# ProPrj_chesslink-v1-pcb_2025-04-17.net
KiCad netlist of a schematic drawn in EasyEDA Pro
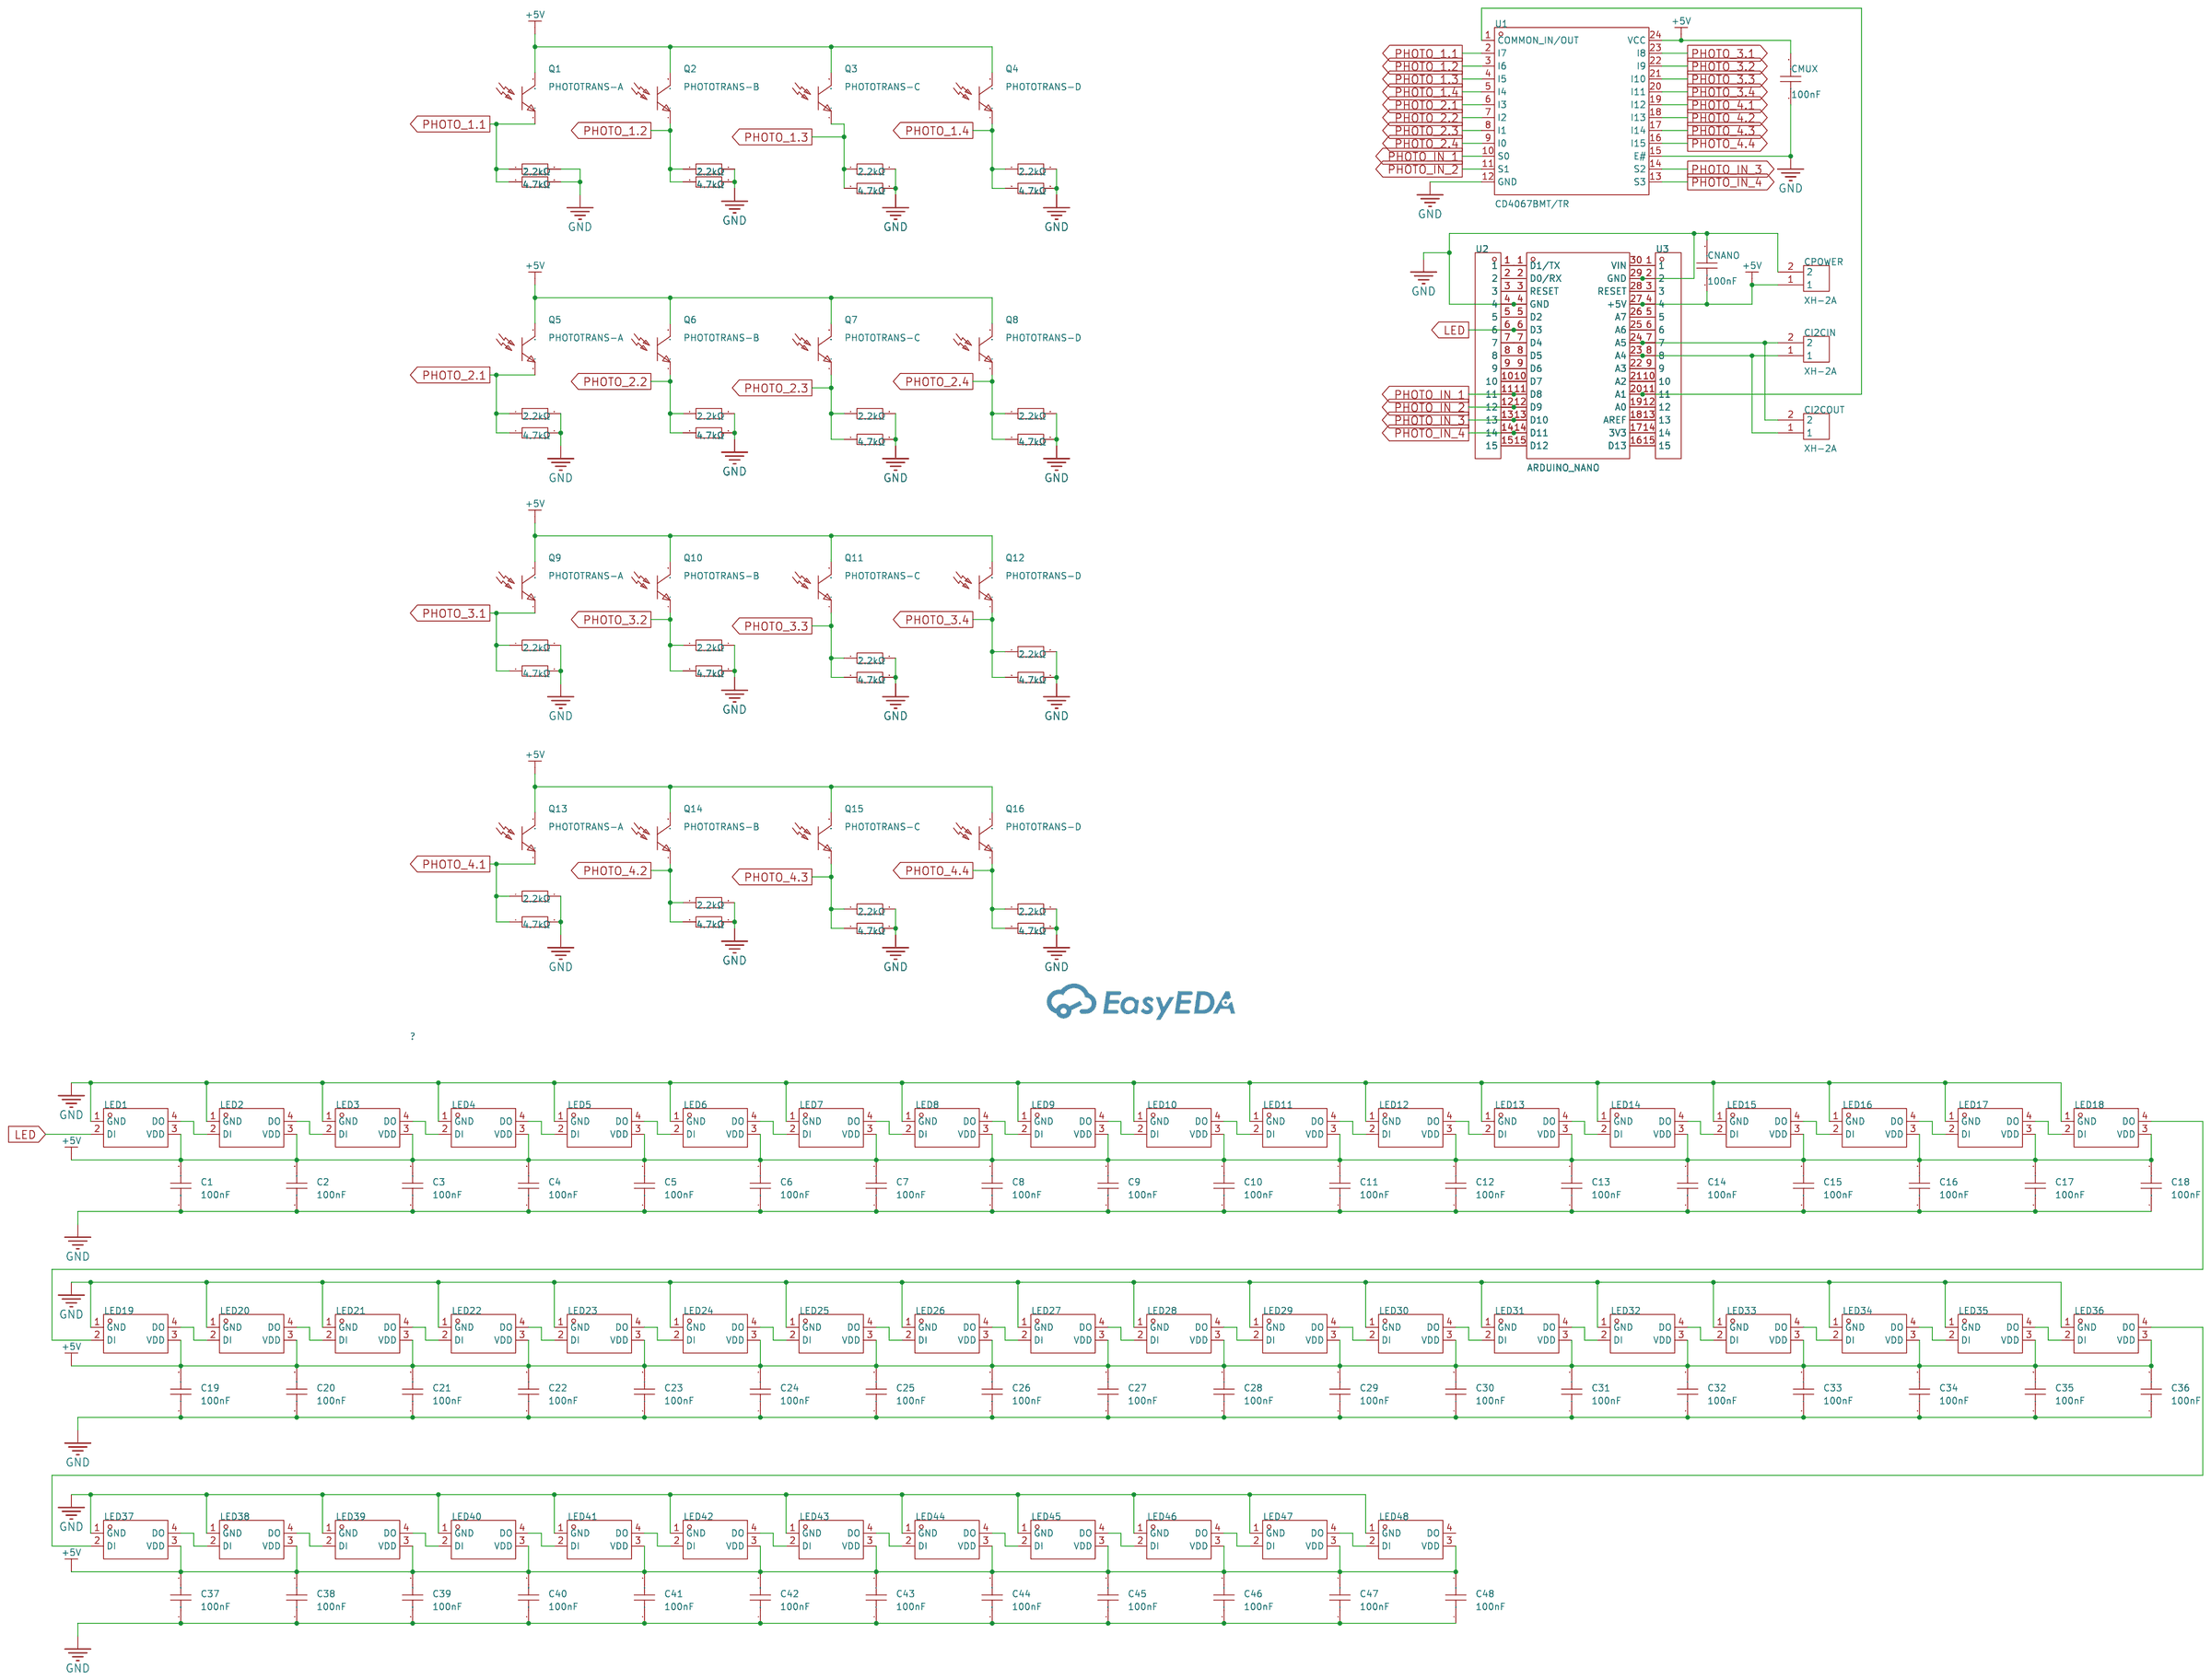
[diagram p0: schematic sheet]

(export (version "E")
  (design (tool "Eeschema 10.0.6"))
  (components
    (comp (ref "ArduinoNano")
      (value "ARDUINO_NANO")
      (footprint "easyedapro:COMM-TH_ARDUINO_NANO")
      (libsource (lib "easyedapro") (part "ARDUINO_NANO"))
    )
    (comp (ref "C1")
      (value "100nF")
      (footprint "easyedapro:C0402")
      (fields
        (field (name "Manufacturer Part") "CL05B104KO5NNNC")
        (field (name "Manufacturer") "SAMSUNG(三星)")
      )
      (libsource (lib "easyedapro") (part "CL05B104KO5NNNC"))
    )
    (comp (ref "C2")
      (value "100nF")
      (footprint "easyedapro:C0402")
      (fields
        (field (name "Manufacturer Part") "CL05B104KO5NNNC")
        (field (name "Manufacturer") "SAMSUNG(三星)")
      )
      (libsource (lib "easyedapro") (part "CL05B104KO5NNNC"))
    )
    (comp (ref "C3")
      (value "100nF")
      (footprint "easyedapro:C0402")
      (fields
        (field (name "Manufacturer Part") "CL05B104KO5NNNC")
        (field (name "Manufacturer") "SAMSUNG(三星)")
      )
      (libsource (lib "easyedapro") (part "CL05B104KO5NNNC"))
    )
    (comp (ref "C4")
      (value "100nF")
      (footprint "easyedapro:C0402")
      (fields
        (field (name "Manufacturer Part") "CL05B104KO5NNNC")
        (field (name "Manufacturer") "SAMSUNG(三星)")
      )
      (libsource (lib "easyedapro") (part "CL05B104KO5NNNC"))
    )
    (comp (ref "C5")
      (value "100nF")
      (footprint "easyedapro:C0402")
      (fields
        (field (name "Manufacturer Part") "CL05B104KO5NNNC")
        (field (name "Manufacturer") "SAMSUNG(三星)")
      )
      (libsource (lib "easyedapro") (part "CL05B104KO5NNNC"))
    )
    (comp (ref "C6")
      (value "100nF")
      (footprint "easyedapro:C0402")
      (fields
        (field (name "Manufacturer Part") "CL05B104KO5NNNC")
        (field (name "Manufacturer") "SAMSUNG(三星)")
      )
      (libsource (lib "easyedapro") (part "CL05B104KO5NNNC"))
    )
    (comp (ref "C7")
      (value "100nF")
      (footprint "easyedapro:C0402")
      (fields
        (field (name "Manufacturer Part") "CL05B104KO5NNNC")
        (field (name "Manufacturer") "SAMSUNG(三星)")
      )
      (libsource (lib "easyedapro") (part "CL05B104KO5NNNC"))
    )
    (comp (ref "C8")
      (value "100nF")
      (footprint "easyedapro:C0402")
      (fields
        (field (name "Manufacturer Part") "CL05B104KO5NNNC")
        (field (name "Manufacturer") "SAMSUNG(三星)")
      )
      (libsource (lib "easyedapro") (part "CL05B104KO5NNNC"))
    )
    (comp (ref "C9")
      (value "100nF")
      (footprint "easyedapro:C0402")
      (fields
        (field (name "Manufacturer Part") "CL05B104KO5NNNC")
        (field (name "Manufacturer") "SAMSUNG(三星)")
      )
      (libsource (lib "easyedapro") (part "CL05B104KO5NNNC"))
    )
    (comp (ref "C10")
      (value "100nF")
      (footprint "easyedapro:C0402")
      (fields
        (field (name "Manufacturer Part") "CL05B104KO5NNNC")
        (field (name "Manufacturer") "SAMSUNG(三星)")
      )
      (libsource (lib "easyedapro") (part "CL05B104KO5NNNC"))
    )
    (comp (ref "C11")
      (value "100nF")
      (footprint "easyedapro:C0402")
      (fields
        (field (name "Manufacturer Part") "CL05B104KO5NNNC")
        (field (name "Manufacturer") "SAMSUNG(三星)")
      )
      (libsource (lib "easyedapro") (part "CL05B104KO5NNNC"))
    )
    (comp (ref "C12")
      (value "100nF")
      (footprint "easyedapro:C0402")
      (fields
        (field (name "Manufacturer Part") "CL05B104KO5NNNC")
        (field (name "Manufacturer") "SAMSUNG(三星)")
      )
      (libsource (lib "easyedapro") (part "CL05B104KO5NNNC"))
    )
    (comp (ref "C13")
      (value "100nF")
      (footprint "easyedapro:C0402")
      (fields
        (field (name "Manufacturer Part") "CL05B104KO5NNNC")
        (field (name "Manufacturer") "SAMSUNG(三星)")
      )
      (libsource (lib "easyedapro") (part "CL05B104KO5NNNC"))
    )
    (comp (ref "C14")
      (value "100nF")
      (footprint "easyedapro:C0402")
      (fields
        (field (name "Manufacturer Part") "CL05B104KO5NNNC")
        (field (name "Manufacturer") "SAMSUNG(三星)")
      )
      (libsource (lib "easyedapro") (part "CL05B104KO5NNNC"))
    )
    (comp (ref "C15")
      (value "100nF")
      (footprint "easyedapro:C0402")
      (fields
        (field (name "Manufacturer Part") "CL05B104KO5NNNC")
        (field (name "Manufacturer") "SAMSUNG(三星)")
      )
      (libsource (lib "easyedapro") (part "CL05B104KO5NNNC"))
    )
    (comp (ref "C16")
      (value "100nF")
      (footprint "easyedapro:C0402")
      (fields
        (field (name "Manufacturer Part") "CL05B104KO5NNNC")
        (field (name "Manufacturer") "SAMSUNG(三星)")
      )
      (libsource (lib "easyedapro") (part "CL05B104KO5NNNC"))
    )
    (comp (ref "C17")
      (value "100nF")
      (footprint "easyedapro:C0402")
      (fields
        (field (name "Manufacturer Part") "CL05B104KO5NNNC")
        (field (name "Manufacturer") "SAMSUNG(三星)")
      )
      (libsource (lib "easyedapro") (part "CL05B104KO5NNNC"))
    )
    (comp (ref "C18")
      (value "100nF")
      (footprint "easyedapro:C0402")
      (fields
        (field (name "Manufacturer Part") "CL05B104KO5NNNC")
        (field (name "Manufacturer") "SAMSUNG(三星)")
      )
      (libsource (lib "easyedapro") (part "CL05B104KO5NNNC"))
    )
    (comp (ref "C19")
      (value "100nF")
      (footprint "easyedapro:C0402")
      (fields
        (field (name "Manufacturer Part") "CL05B104KO5NNNC")
        (field (name "Manufacturer") "SAMSUNG(三星)")
      )
      (libsource (lib "easyedapro") (part "CL05B104KO5NNNC"))
    )
    (comp (ref "C20")
      (value "100nF")
      (footprint "easyedapro:C0402")
      (fields
        (field (name "Manufacturer Part") "CL05B104KO5NNNC")
        (field (name "Manufacturer") "SAMSUNG(三星)")
      )
      (libsource (lib "easyedapro") (part "CL05B104KO5NNNC"))
    )
    (comp (ref "C21")
      (value "100nF")
      (footprint "easyedapro:C0402")
      (fields
        (field (name "Manufacturer Part") "CL05B104KO5NNNC")
        (field (name "Manufacturer") "SAMSUNG(三星)")
      )
      (libsource (lib "easyedapro") (part "CL05B104KO5NNNC"))
    )
    (comp (ref "C22")
      (value "100nF")
      (footprint "easyedapro:C0402")
      (fields
        (field (name "Manufacturer Part") "CL05B104KO5NNNC")
        (field (name "Manufacturer") "SAMSUNG(三星)")
      )
      (libsource (lib "easyedapro") (part "CL05B104KO5NNNC"))
    )
    (comp (ref "C23")
      (value "100nF")
      (footprint "easyedapro:C0402")
      (fields
        (field (name "Manufacturer Part") "CL05B104KO5NNNC")
        (field (name "Manufacturer") "SAMSUNG(三星)")
      )
      (libsource (lib "easyedapro") (part "CL05B104KO5NNNC"))
    )
    (comp (ref "C24")
      (value "100nF")
      (footprint "easyedapro:C0402")
      (fields
        (field (name "Manufacturer Part") "CL05B104KO5NNNC")
        (field (name "Manufacturer") "SAMSUNG(三星)")
      )
      (libsource (lib "easyedapro") (part "CL05B104KO5NNNC"))
    )
    (comp (ref "C25")
      (value "100nF")
      (footprint "easyedapro:C0402")
      (fields
        (field (name "Manufacturer Part") "CL05B104KO5NNNC")
        (field (name "Manufacturer") "SAMSUNG(三星)")
      )
      (libsource (lib "easyedapro") (part "CL05B104KO5NNNC"))
    )
    (comp (ref "C26")
      (value "100nF")
      (footprint "easyedapro:C0402")
      (fields
        (field (name "Manufacturer Part") "CL05B104KO5NNNC")
        (field (name "Manufacturer") "SAMSUNG(三星)")
      )
      (libsource (lib "easyedapro") (part "CL05B104KO5NNNC"))
    )
    (comp (ref "C27")
      (value "100nF")
      (footprint "easyedapro:C0402")
      (fields
        (field (name "Manufacturer Part") "CL05B104KO5NNNC")
        (field (name "Manufacturer") "SAMSUNG(三星)")
      )
      (libsource (lib "easyedapro") (part "CL05B104KO5NNNC"))
    )
    (comp (ref "C28")
      (value "100nF")
      (footprint "easyedapro:C0402")
      (fields
        (field (name "Manufacturer Part") "CL05B104KO5NNNC")
        (field (name "Manufacturer") "SAMSUNG(三星)")
      )
      (libsource (lib "easyedapro") (part "CL05B104KO5NNNC"))
    )
    (comp (ref "C29")
      (value "100nF")
      (footprint "easyedapro:C0402")
      (fields
        (field (name "Manufacturer Part") "CL05B104KO5NNNC")
        (field (name "Manufacturer") "SAMSUNG(三星)")
      )
      (libsource (lib "easyedapro") (part "CL05B104KO5NNNC"))
    )
    (comp (ref "C30")
      (value "100nF")
      (footprint "easyedapro:C0402")
      (fields
        (field (name "Manufacturer Part") "CL05B104KO5NNNC")
        (field (name "Manufacturer") "SAMSUNG(三星)")
      )
      (libsource (lib "easyedapro") (part "CL05B104KO5NNNC"))
    )
    (comp (ref "C31")
      (value "100nF")
      (footprint "easyedapro:C0402")
      (fields
        (field (name "Manufacturer Part") "CL05B104KO5NNNC")
        (field (name "Manufacturer") "SAMSUNG(三星)")
      )
      (libsource (lib "easyedapro") (part "CL05B104KO5NNNC"))
    )
    (comp (ref "C32")
      (value "100nF")
      (footprint "easyedapro:C0402")
      (fields
        (field (name "Manufacturer Part") "CL05B104KO5NNNC")
        (field (name "Manufacturer") "SAMSUNG(三星)")
      )
      (libsource (lib "easyedapro") (part "CL05B104KO5NNNC"))
    )
    (comp (ref "C33")
      (value "100nF")
      (footprint "easyedapro:C0402")
      (fields
        (field (name "Manufacturer Part") "CL05B104KO5NNNC")
        (field (name "Manufacturer") "SAMSUNG(三星)")
      )
      (libsource (lib "easyedapro") (part "CL05B104KO5NNNC"))
    )
    (comp (ref "C34")
      (value "100nF")
      (footprint "easyedapro:C0402")
      (fields
        (field (name "Manufacturer Part") "CL05B104KO5NNNC")
        (field (name "Manufacturer") "SAMSUNG(三星)")
      )
      (libsource (lib "easyedapro") (part "CL05B104KO5NNNC"))
    )
    (comp (ref "C35")
      (value "100nF")
      (footprint "easyedapro:C0402")
      (fields
        (field (name "Manufacturer Part") "CL05B104KO5NNNC")
        (field (name "Manufacturer") "SAMSUNG(三星)")
      )
      (libsource (lib "easyedapro") (part "CL05B104KO5NNNC"))
    )
    (comp (ref "C36")
      (value "100nF")
      (footprint "easyedapro:C0402")
      (fields
        (field (name "Manufacturer Part") "CL05B104KO5NNNC")
        (field (name "Manufacturer") "SAMSUNG(三星)")
      )
      (libsource (lib "easyedapro") (part "CL05B104KO5NNNC"))
    )
    (comp (ref "C37")
      (value "100nF")
      (footprint "easyedapro:C0402")
      (fields
        (field (name "Manufacturer Part") "CL05B104KO5NNNC")
        (field (name "Manufacturer") "SAMSUNG(三星)")
      )
      (libsource (lib "easyedapro") (part "CL05B104KO5NNNC"))
    )
    (comp (ref "C38")
      (value "100nF")
      (footprint "easyedapro:C0402")
      (fields
        (field (name "Manufacturer Part") "CL05B104KO5NNNC")
        (field (name "Manufacturer") "SAMSUNG(三星)")
      )
      (libsource (lib "easyedapro") (part "CL05B104KO5NNNC"))
    )
    (comp (ref "C39")
      (value "100nF")
      (footprint "easyedapro:C0402")
      (fields
        (field (name "Manufacturer Part") "CL05B104KO5NNNC")
        (field (name "Manufacturer") "SAMSUNG(三星)")
      )
      (libsource (lib "easyedapro") (part "CL05B104KO5NNNC"))
    )
    (comp (ref "C40")
      (value "100nF")
      (footprint "easyedapro:C0402")
      (fields
        (field (name "Manufacturer Part") "CL05B104KO5NNNC")
        (field (name "Manufacturer") "SAMSUNG(三星)")
      )
      (libsource (lib "easyedapro") (part "CL05B104KO5NNNC"))
    )
    (comp (ref "C41")
      (value "100nF")
      (footprint "easyedapro:C0402")
      (fields
        (field (name "Manufacturer Part") "CL05B104KO5NNNC")
        (field (name "Manufacturer") "SAMSUNG(三星)")
      )
      (libsource (lib "easyedapro") (part "CL05B104KO5NNNC"))
    )
    (comp (ref "C42")
      (value "100nF")
      (footprint "easyedapro:C0402")
      (fields
        (field (name "Manufacturer Part") "CL05B104KO5NNNC")
        (field (name "Manufacturer") "SAMSUNG(三星)")
      )
      (libsource (lib "easyedapro") (part "CL05B104KO5NNNC"))
    )
    (comp (ref "C43")
      (value "100nF")
      (footprint "easyedapro:C0402")
      (fields
        (field (name "Manufacturer Part") "CL05B104KO5NNNC")
        (field (name "Manufacturer") "SAMSUNG(三星)")
      )
      (libsource (lib "easyedapro") (part "CL05B104KO5NNNC"))
    )
    (comp (ref "C44")
      (value "100nF")
      (footprint "easyedapro:C0402")
      (fields
        (field (name "Manufacturer Part") "CL05B104KO5NNNC")
        (field (name "Manufacturer") "SAMSUNG(三星)")
      )
      (libsource (lib "easyedapro") (part "CL05B104KO5NNNC"))
    )
    (comp (ref "C45")
      (value "100nF")
      (footprint "easyedapro:C0402")
      (fields
        (field (name "Manufacturer Part") "CL05B104KO5NNNC")
        (field (name "Manufacturer") "SAMSUNG(三星)")
      )
      (libsource (lib "easyedapro") (part "CL05B104KO5NNNC"))
    )
    (comp (ref "C46")
      (value "100nF")
      (footprint "easyedapro:C0402")
      (fields
        (field (name "Manufacturer Part") "CL05B104KO5NNNC")
        (field (name "Manufacturer") "SAMSUNG(三星)")
      )
      (libsource (lib "easyedapro") (part "CL05B104KO5NNNC"))
    )
    (comp (ref "C47")
      (value "100nF")
      (footprint "easyedapro:C0402")
      (fields
        (field (name "Manufacturer Part") "CL05B104KO5NNNC")
        (field (name "Manufacturer") "SAMSUNG(三星)")
      )
      (libsource (lib "easyedapro") (part "CL05B104KO5NNNC"))
    )
    (comp (ref "C48")
      (value "100nF")
      (footprint "easyedapro:C0402")
      (fields
        (field (name "Manufacturer Part") "CL05B104KO5NNNC")
        (field (name "Manufacturer") "SAMSUNG(三星)")
      )
      (libsource (lib "easyedapro") (part "CL05B104KO5NNNC"))
    )
    (comp (ref "CI2CIN")
      (value "XH-2A")
      (footprint "easyedapro:CONN-TH_XH-2A")
      (fields (field (name "Manufacturer") "BOOMELE(博穆精密)"))
      (libsource (lib "easyedapro") (part "XH-2A"))
    )
    (comp (ref "CI2COUT")
      (value "XH-2A")
      (footprint "easyedapro:CONN-TH_XH-2A")
      (fields (field (name "Manufacturer") "BOOMELE(博穆精密)"))
      (libsource (lib "easyedapro") (part "XH-2A"))
    )
    (comp (ref "CMUX")
      (value "100nF")
      (footprint "easyedapro:C0402")
      (fields
        (field (name "Manufacturer Part") "CL05B104KO5NNNC")
        (field (name "Manufacturer") "SAMSUNG(三星)")
      )
      (libsource (lib "easyedapro") (part "CL05B104KO5NNNC"))
    )
    (comp (ref "CNANO")
      (value "100nF")
      (footprint "easyedapro:C0402")
      (fields
        (field (name "Manufacturer Part") "CL05B104KO5NNNC")
        (field (name "Manufacturer") "SAMSUNG(三星)")
      )
      (libsource (lib "easyedapro") (part "CL05B104KO5NNNC"))
    )
    (comp (ref "CPOWER")
      (value "XH-2A")
      (footprint "easyedapro:CONN-TH_XH-2A")
      (fields (field (name "Manufacturer") "BOOMELE(博穆精密)"))
      (libsource (lib "easyedapro") (part "XH-2A"))
    )
    (comp (ref "LED1")
      (value "XL-1615RGBC-WS2812B")
      (fields (field (name "Manufacturer") "XINGLIGHT(成兴光)"))
      (libsource (lib "easyedapro") (part "XL-2121RGBC-WS2812B"))
    )
    (comp (ref "LED2")
      (value "XL-1615RGBC-WS2812B")
      (fields (field (name "Manufacturer") "XINGLIGHT(成兴光)"))
      (libsource (lib "easyedapro") (part "XL-2121RGBC-WS2812B"))
    )
    (comp (ref "LED3")
      (value "XL-1615RGBC-WS2812B")
      (fields (field (name "Manufacturer") "XINGLIGHT(成兴光)"))
      (libsource (lib "easyedapro") (part "XL-2121RGBC-WS2812B"))
    )
    (comp (ref "LED4")
      (value "XL-1615RGBC-WS2812B")
      (fields (field (name "Manufacturer") "XINGLIGHT(成兴光)"))
      (libsource (lib "easyedapro") (part "XL-2121RGBC-WS2812B"))
    )
    (comp (ref "LED5")
      (value "XL-1615RGBC-WS2812B")
      (fields (field (name "Manufacturer") "XINGLIGHT(成兴光)"))
      (libsource (lib "easyedapro") (part "XL-2121RGBC-WS2812B"))
    )
    (comp (ref "LED6")
      (value "XL-1615RGBC-WS2812B")
      (fields (field (name "Manufacturer") "XINGLIGHT(成兴光)"))
      (libsource (lib "easyedapro") (part "XL-2121RGBC-WS2812B"))
    )
    (comp (ref "LED7")
      (value "XL-1615RGBC-WS2812B")
      (fields (field (name "Manufacturer") "XINGLIGHT(成兴光)"))
      (libsource (lib "easyedapro") (part "XL-2121RGBC-WS2812B"))
    )
    (comp (ref "LED8")
      (value "XL-1615RGBC-WS2812B")
      (fields (field (name "Manufacturer") "XINGLIGHT(成兴光)"))
      (libsource (lib "easyedapro") (part "XL-2121RGBC-WS2812B"))
    )
    (comp (ref "LED9")
      (value "XL-1615RGBC-WS2812B")
      (fields (field (name "Manufacturer") "XINGLIGHT(成兴光)"))
      (libsource (lib "easyedapro") (part "XL-2121RGBC-WS2812B"))
    )
    (comp (ref "LED10")
      (value "XL-1615RGBC-WS2812B")
      (fields (field (name "Manufacturer") "XINGLIGHT(成兴光)"))
      (libsource (lib "easyedapro") (part "XL-2121RGBC-WS2812B"))
    )
    (comp (ref "LED11")
      (value "XL-1615RGBC-WS2812B")
      (fields (field (name "Manufacturer") "XINGLIGHT(成兴光)"))
      (libsource (lib "easyedapro") (part "XL-2121RGBC-WS2812B"))
    )
    (comp (ref "LED12")
      (value "XL-1615RGBC-WS2812B")
      (fields (field (name "Manufacturer") "XINGLIGHT(成兴光)"))
      (libsource (lib "easyedapro") (part "XL-2121RGBC-WS2812B"))
    )
    (comp (ref "LED13")
      (value "XL-1615RGBC-WS2812B")
      (fields (field (name "Manufacturer") "XINGLIGHT(成兴光)"))
      (libsource (lib "easyedapro") (part "XL-2121RGBC-WS2812B"))
    )
    (comp (ref "LED14")
      (value "XL-1615RGBC-WS2812B")
      (fields (field (name "Manufacturer") "XINGLIGHT(成兴光)"))
      (libsource (lib "easyedapro") (part "XL-2121RGBC-WS2812B"))
    )
    (comp (ref "LED15")
      (value "XL-1615RGBC-WS2812B")
      (fields (field (name "Manufacturer") "XINGLIGHT(成兴光)"))
      (libsource (lib "easyedapro") (part "XL-2121RGBC-WS2812B"))
    )
    (comp (ref "LED16")
      (value "XL-1615RGBC-WS2812B")
      (fields (field (name "Manufacturer") "XINGLIGHT(成兴光)"))
      (libsource (lib "easyedapro") (part "XL-2121RGBC-WS2812B"))
    )
    (comp (ref "LED17")
      (value "XL-1615RGBC-WS2812B")
      (fields (field (name "Manufacturer") "XINGLIGHT(成兴光)"))
      (libsource (lib "easyedapro") (part "XL-2121RGBC-WS2812B"))
    )
    (comp (ref "LED18")
      (value "XL-1615RGBC-WS2812B")
      (fields (field (name "Manufacturer") "XINGLIGHT(成兴光)"))
      (libsource (lib "easyedapro") (part "XL-2121RGBC-WS2812B"))
    )
    (comp (ref "LED19")
      (value "XL-1615RGBC-WS2812B")
      (fields (field (name "Manufacturer") "XINGLIGHT(成兴光)"))
      (libsource (lib "easyedapro") (part "XL-2121RGBC-WS2812B"))
    )
    (comp (ref "LED20")
      (value "XL-1615RGBC-WS2812B")
      (fields (field (name "Manufacturer") "XINGLIGHT(成兴光)"))
      (libsource (lib "easyedapro") (part "XL-2121RGBC-WS2812B"))
    )
    (comp (ref "LED21")
      (value "XL-1615RGBC-WS2812B")
      (fields (field (name "Manufacturer") "XINGLIGHT(成兴光)"))
      (libsource (lib "easyedapro") (part "XL-2121RGBC-WS2812B"))
    )
    (comp (ref "LED22")
      (value "XL-1615RGBC-WS2812B")
      (fields (field (name "Manufacturer") "XINGLIGHT(成兴光)"))
      (libsource (lib "easyedapro") (part "XL-2121RGBC-WS2812B"))
    )
    (comp (ref "LED23")
      (value "XL-1615RGBC-WS2812B")
      (fields (field (name "Manufacturer") "XINGLIGHT(成兴光)"))
      (libsource (lib "easyedapro") (part "XL-2121RGBC-WS2812B"))
    )
    (comp (ref "LED24")
      (value "XL-1615RGBC-WS2812B")
      (fields (field (name "Manufacturer") "XINGLIGHT(成兴光)"))
      (libsource (lib "easyedapro") (part "XL-2121RGBC-WS2812B"))
    )
    (comp (ref "LED25")
      (value "XL-1615RGBC-WS2812B")
      (fields (field (name "Manufacturer") "XINGLIGHT(成兴光)"))
      (libsource (lib "easyedapro") (part "XL-2121RGBC-WS2812B"))
    )
    (comp (ref "LED26")
      (value "XL-1615RGBC-WS2812B")
      (fields (field (name "Manufacturer") "XINGLIGHT(成兴光)"))
      (libsource (lib "easyedapro") (part "XL-2121RGBC-WS2812B"))
    )
    (comp (ref "LED27")
      (value "XL-1615RGBC-WS2812B")
      (fields (field (name "Manufacturer") "XINGLIGHT(成兴光)"))
      (libsource (lib "easyedapro") (part "XL-2121RGBC-WS2812B"))
    )
    (comp (ref "LED28")
      (value "XL-1615RGBC-WS2812B")
      (fields (field (name "Manufacturer") "XINGLIGHT(成兴光)"))
      (libsource (lib "easyedapro") (part "XL-2121RGBC-WS2812B"))
    )
    (comp (ref "LED29")
      (value "XL-1615RGBC-WS2812B")
      (fields (field (name "Manufacturer") "XINGLIGHT(成兴光)"))
      (libsource (lib "easyedapro") (part "XL-2121RGBC-WS2812B"))
    )
    (comp (ref "LED30")
      (value "XL-1615RGBC-WS2812B")
      (fields (field (name "Manufacturer") "XINGLIGHT(成兴光)"))
      (libsource (lib "easyedapro") (part "XL-2121RGBC-WS2812B"))
    )
    (comp (ref "LED31")
      (value "XL-1615RGBC-WS2812B")
      (fields (field (name "Manufacturer") "XINGLIGHT(成兴光)"))
      (libsource (lib "easyedapro") (part "XL-2121RGBC-WS2812B"))
    )
    (comp (ref "LED32")
      (value "XL-1615RGBC-WS2812B")
      (fields (field (name "Manufacturer") "XINGLIGHT(成兴光)"))
      (libsource (lib "easyedapro") (part "XL-2121RGBC-WS2812B"))
    )
    (comp (ref "LED33")
      (value "XL-1615RGBC-WS2812B")
      (fields (field (name "Manufacturer") "XINGLIGHT(成兴光)"))
      (libsource (lib "easyedapro") (part "XL-2121RGBC-WS2812B"))
    )
    (comp (ref "LED34")
      (value "XL-1615RGBC-WS2812B")
      (fields (field (name "Manufacturer") "XINGLIGHT(成兴光)"))
      (libsource (lib "easyedapro") (part "XL-2121RGBC-WS2812B"))
    )
    (comp (ref "LED35")
      (value "XL-1615RGBC-WS2812B")
      (fields (field (name "Manufacturer") "XINGLIGHT(成兴光)"))
      (libsource (lib "easyedapro") (part "XL-2121RGBC-WS2812B"))
    )
    (comp (ref "LED36")
      (value "XL-1615RGBC-WS2812B")
      (fields (field (name "Manufacturer") "XINGLIGHT(成兴光)"))
      (libsource (lib "easyedapro") (part "XL-2121RGBC-WS2812B"))
    )
    (comp (ref "LED37")
      (value "XL-1615RGBC-WS2812B")
      (fields (field (name "Manufacturer") "XINGLIGHT(成兴光)"))
      (libsource (lib "easyedapro") (part "XL-2121RGBC-WS2812B"))
    )
    (comp (ref "LED38")
      (value "XL-1615RGBC-WS2812B")
      (fields (field (name "Manufacturer") "XINGLIGHT(成兴光)"))
      (libsource (lib "easyedapro") (part "XL-2121RGBC-WS2812B"))
    )
    (comp (ref "LED39")
      (value "XL-1615RGBC-WS2812B")
      (fields (field (name "Manufacturer") "XINGLIGHT(成兴光)"))
      (libsource (lib "easyedapro") (part "XL-2121RGBC-WS2812B"))
    )
    (comp (ref "LED40")
      (value "XL-1615RGBC-WS2812B")
      (fields (field (name "Manufacturer") "XINGLIGHT(成兴光)"))
      (libsource (lib "easyedapro") (part "XL-2121RGBC-WS2812B"))
    )
    (comp (ref "LED41")
      (value "XL-1615RGBC-WS2812B")
      (fields (field (name "Manufacturer") "XINGLIGHT(成兴光)"))
      (libsource (lib "easyedapro") (part "XL-2121RGBC-WS2812B"))
    )
    (comp (ref "LED42")
      (value "XL-1615RGBC-WS2812B")
      (fields (field (name "Manufacturer") "XINGLIGHT(成兴光)"))
      (libsource (lib "easyedapro") (part "XL-2121RGBC-WS2812B"))
    )
    (comp (ref "LED43")
      (value "XL-1615RGBC-WS2812B")
      (fields (field (name "Manufacturer") "XINGLIGHT(成兴光)"))
      (libsource (lib "easyedapro") (part "XL-2121RGBC-WS2812B"))
    )
    (comp (ref "LED44")
      (value "XL-1615RGBC-WS2812B")
      (fields (field (name "Manufacturer") "XINGLIGHT(成兴光)"))
      (libsource (lib "easyedapro") (part "XL-2121RGBC-WS2812B"))
    )
    (comp (ref "LED45")
      (value "XL-1615RGBC-WS2812B")
      (fields (field (name "Manufacturer") "XINGLIGHT(成兴光)"))
      (libsource (lib "easyedapro") (part "XL-2121RGBC-WS2812B"))
    )
    (comp (ref "LED46")
      (value "XL-1615RGBC-WS2812B")
      (fields (field (name "Manufacturer") "XINGLIGHT(成兴光)"))
      (libsource (lib "easyedapro") (part "XL-2121RGBC-WS2812B"))
    )
    (comp (ref "LED47")
      (value "XL-1615RGBC-WS2812B")
      (fields (field (name "Manufacturer") "XINGLIGHT(成兴光)"))
      (libsource (lib "easyedapro") (part "XL-2121RGBC-WS2812B"))
    )
    (comp (ref "LED48")
      (value "XL-1615RGBC-WS2812B")
      (fields (field (name "Manufacturer") "XINGLIGHT(成兴光)"))
      (libsource (lib "easyedapro") (part "XL-2121RGBC-WS2812B"))
    )
    (comp (ref "Q1")
      (value "PHOTOTRANS-A")
      (footprint "easyedapro:OPTO-SMD_L2.0-W1.3-R-FD")
      (fields
        (field (name "Manufacturer Part") "PT17-21C/L41/TR8")
        (field (name "Manufacturer") "EVERLIGHT(亿光)")
      )
      (libsource (lib "easyedapro") (part "PT17-21C/L41/TR8"))
    )
    (comp (ref "Q2")
      (value "PHOTOTRANS-B")
      (footprint "easyedapro:OPTO-SMD_L2.0-W1.3-R-FD")
      (fields
        (field (name "Manufacturer Part") "PT17-21C/L41/TR8")
        (field (name "Manufacturer") "EVERLIGHT(亿光)")
      )
      (libsource (lib "easyedapro") (part "PT17-21C/L41/TR8"))
    )
    (comp (ref "Q3")
      (value "PHOTOTRANS-C")
      (footprint "easyedapro:OPTO-SMD_L2.0-W1.3-R-FD")
      (fields
        (field (name "Manufacturer Part") "PT17-21C/L41/TR8")
        (field (name "Manufacturer") "EVERLIGHT(亿光)")
      )
      (libsource (lib "easyedapro") (part "PT17-21C/L41/TR8"))
    )
    (comp (ref "Q4")
      (value "PHOTOTRANS-D")
      (footprint "easyedapro:OPTO-SMD_L2.0-W1.3-R-FD")
      (fields
        (field (name "Manufacturer Part") "PT17-21C/L41/TR8")
        (field (name "Manufacturer") "EVERLIGHT(亿光)")
      )
      (libsource (lib "easyedapro") (part "PT17-21C/L41/TR8"))
    )
    (comp (ref "Q5")
      (value "PHOTOTRANS-A")
      (footprint "easyedapro:OPTO-SMD_L2.0-W1.3-R-FD")
      (fields
        (field (name "Manufacturer Part") "PT17-21C/L41/TR8")
        (field (name "Manufacturer") "EVERLIGHT(亿光)")
      )
      (libsource (lib "easyedapro") (part "PT17-21C/L41/TR8"))
    )
    (comp (ref "Q6")
      (value "PHOTOTRANS-B")
      (footprint "easyedapro:OPTO-SMD_L2.0-W1.3-R-FD")
      (fields
        (field (name "Manufacturer Part") "PT17-21C/L41/TR8")
        (field (name "Manufacturer") "EVERLIGHT(亿光)")
      )
      (libsource (lib "easyedapro") (part "PT17-21C/L41/TR8"))
    )
    (comp (ref "Q7")
      (value "PHOTOTRANS-C")
      (footprint "easyedapro:OPTO-SMD_L2.0-W1.3-R-FD")
      (fields
        (field (name "Manufacturer Part") "PT17-21C/L41/TR8")
        (field (name "Manufacturer") "EVERLIGHT(亿光)")
      )
      (libsource (lib "easyedapro") (part "PT17-21C/L41/TR8"))
    )
    (comp (ref "Q8")
      (value "PHOTOTRANS-D")
      (footprint "easyedapro:OPTO-SMD_L2.0-W1.3-R-FD")
      (fields
        (field (name "Manufacturer Part") "PT17-21C/L41/TR8")
        (field (name "Manufacturer") "EVERLIGHT(亿光)")
      )
      (libsource (lib "easyedapro") (part "PT17-21C/L41/TR8"))
    )
    (comp (ref "Q9")
      (value "PHOTOTRANS-A")
      (footprint "easyedapro:OPTO-SMD_L2.0-W1.3-R-FD")
      (fields
        (field (name "Manufacturer Part") "PT17-21C/L41/TR8")
        (field (name "Manufacturer") "EVERLIGHT(亿光)")
      )
      (libsource (lib "easyedapro") (part "PT17-21C/L41/TR8"))
    )
    (comp (ref "Q10")
      (value "PHOTOTRANS-B")
      (footprint "easyedapro:OPTO-SMD_L2.0-W1.3-R-FD")
      (fields
        (field (name "Manufacturer Part") "PT17-21C/L41/TR8")
        (field (name "Manufacturer") "EVERLIGHT(亿光)")
      )
      (libsource (lib "easyedapro") (part "PT17-21C/L41/TR8"))
    )
    (comp (ref "Q11")
      (value "PHOTOTRANS-C")
      (footprint "easyedapro:OPTO-SMD_L2.0-W1.3-R-FD")
      (fields
        (field (name "Manufacturer Part") "PT17-21C/L41/TR8")
        (field (name "Manufacturer") "EVERLIGHT(亿光)")
      )
      (libsource (lib "easyedapro") (part "PT17-21C/L41/TR8"))
    )
    (comp (ref "Q12")
      (value "PHOTOTRANS-D")
      (footprint "easyedapro:OPTO-SMD_L2.0-W1.3-R-FD")
      (fields
        (field (name "Manufacturer Part") "PT17-21C/L41/TR8")
        (field (name "Manufacturer") "EVERLIGHT(亿光)")
      )
      (libsource (lib "easyedapro") (part "PT17-21C/L41/TR8"))
    )
    (comp (ref "Q13")
      (value "PHOTOTRANS-A")
      (footprint "easyedapro:OPTO-SMD_L2.0-W1.3-R-FD")
      (fields
        (field (name "Manufacturer Part") "PT17-21C/L41/TR8")
        (field (name "Manufacturer") "EVERLIGHT(亿光)")
      )
      (libsource (lib "easyedapro") (part "PT17-21C/L41/TR8"))
    )
    (comp (ref "Q14")
      (value "PHOTOTRANS-B")
      (footprint "easyedapro:OPTO-SMD_L2.0-W1.3-R-FD")
      (fields
        (field (name "Manufacturer Part") "PT17-21C/L41/TR8")
        (field (name "Manufacturer") "EVERLIGHT(亿光)")
      )
      (libsource (lib "easyedapro") (part "PT17-21C/L41/TR8"))
    )
    (comp (ref "Q15")
      (value "PHOTOTRANS-C")
      (footprint "easyedapro:OPTO-SMD_L2.0-W1.3-R-FD")
      (fields
        (field (name "Manufacturer Part") "PT17-21C/L41/TR8")
        (field (name "Manufacturer") "EVERLIGHT(亿光)")
      )
      (libsource (lib "easyedapro") (part "PT17-21C/L41/TR8"))
    )
    (comp (ref "Q16")
      (value "PHOTOTRANS-D")
      (footprint "easyedapro:OPTO-SMD_L2.0-W1.3-R-FD")
      (fields
        (field (name "Manufacturer Part") "PT17-21C/L41/TR8")
        (field (name "Manufacturer") "EVERLIGHT(亿光)")
      )
      (libsource (lib "easyedapro") (part "PT17-21C/L41/TR8"))
    )
    (comp (ref "R1")
      (value "4.7kΩ")
      (footprint "easyedapro:R0603")
      (fields
        (field (name "Manufacturer Part") "0603WAF4701T5E")
        (field (name "Manufacturer") "UNI-ROYAL(厚声)")
      )
      (libsource (lib "easyedapro") (part "0603WAF4701T5E"))
    )
    (comp (ref "R2")
      (value "4.7kΩ")
      (footprint "easyedapro:R0603")
      (fields
        (field (name "Manufacturer Part") "0603WAF4701T5E")
        (field (name "Manufacturer") "UNI-ROYAL(厚声)")
      )
      (libsource (lib "easyedapro") (part "0603WAF4701T5E"))
    )
    (comp (ref "R3")
      (value "4.7kΩ")
      (footprint "easyedapro:R0603")
      (fields
        (field (name "Manufacturer Part") "0603WAF4701T5E")
        (field (name "Manufacturer") "UNI-ROYAL(厚声)")
      )
      (libsource (lib "easyedapro") (part "0603WAF4701T5E"))
    )
    (comp (ref "R4")
      (value "4.7kΩ")
      (footprint "easyedapro:R0603")
      (fields
        (field (name "Manufacturer Part") "0603WAF4701T5E")
        (field (name "Manufacturer") "UNI-ROYAL(厚声)")
      )
      (libsource (lib "easyedapro") (part "0603WAF4701T5E"))
    )
    (comp (ref "R5")
      (value "4.7kΩ")
      (footprint "easyedapro:R0603")
      (fields
        (field (name "Manufacturer Part") "0603WAF4701T5E")
        (field (name "Manufacturer") "UNI-ROYAL(厚声)")
      )
      (libsource (lib "easyedapro") (part "0603WAF4701T5E"))
    )
    (comp (ref "R6")
      (value "4.7kΩ")
      (footprint "easyedapro:R0603")
      (fields
        (field (name "Manufacturer Part") "0603WAF4701T5E")
        (field (name "Manufacturer") "UNI-ROYAL(厚声)")
      )
      (libsource (lib "easyedapro") (part "0603WAF4701T5E"))
    )
    (comp (ref "R7")
      (value "4.7kΩ")
      (footprint "easyedapro:R0603")
      (fields
        (field (name "Manufacturer Part") "0603WAF4701T5E")
        (field (name "Manufacturer") "UNI-ROYAL(厚声)")
      )
      (libsource (lib "easyedapro") (part "0603WAF4701T5E"))
    )
    (comp (ref "R8")
      (value "4.7kΩ")
      (footprint "easyedapro:R0603")
      (fields
        (field (name "Manufacturer Part") "0603WAF4701T5E")
        (field (name "Manufacturer") "UNI-ROYAL(厚声)")
      )
      (libsource (lib "easyedapro") (part "0603WAF4701T5E"))
    )
    (comp (ref "R9")
      (value "4.7kΩ")
      (footprint "easyedapro:R0603")
      (fields
        (field (name "Manufacturer Part") "0603WAF4701T5E")
        (field (name "Manufacturer") "UNI-ROYAL(厚声)")
      )
      (libsource (lib "easyedapro") (part "0603WAF4701T5E"))
    )
    (comp (ref "R10")
      (value "4.7kΩ")
      (footprint "easyedapro:R0603")
      (fields
        (field (name "Manufacturer Part") "0603WAF4701T5E")
        (field (name "Manufacturer") "UNI-ROYAL(厚声)")
      )
      (libsource (lib "easyedapro") (part "0603WAF4701T5E"))
    )
    (comp (ref "R11")
      (value "4.7kΩ")
      (footprint "easyedapro:R0603")
      (fields
        (field (name "Manufacturer Part") "0603WAF4701T5E")
        (field (name "Manufacturer") "UNI-ROYAL(厚声)")
      )
      (libsource (lib "easyedapro") (part "0603WAF4701T5E"))
    )
    (comp (ref "R12")
      (value "4.7kΩ")
      (footprint "easyedapro:R0603")
      (fields
        (field (name "Manufacturer Part") "0603WAF4701T5E")
        (field (name "Manufacturer") "UNI-ROYAL(厚声)")
      )
      (libsource (lib "easyedapro") (part "0603WAF4701T5E"))
    )
    (comp (ref "R13")
      (value "4.7kΩ")
      (footprint "easyedapro:R0603")
      (fields
        (field (name "Manufacturer Part") "0603WAF4701T5E")
        (field (name "Manufacturer") "UNI-ROYAL(厚声)")
      )
      (libsource (lib "easyedapro") (part "0603WAF4701T5E"))
    )
    (comp (ref "R14")
      (value "4.7kΩ")
      (footprint "easyedapro:R0603")
      (fields
        (field (name "Manufacturer Part") "0603WAF4701T5E")
        (field (name "Manufacturer") "UNI-ROYAL(厚声)")
      )
      (libsource (lib "easyedapro") (part "0603WAF4701T5E"))
    )
    (comp (ref "R15")
      (value "4.7kΩ")
      (footprint "easyedapro:R0603")
      (fields
        (field (name "Manufacturer Part") "0603WAF4701T5E")
        (field (name "Manufacturer") "UNI-ROYAL(厚声)")
      )
      (libsource (lib "easyedapro") (part "0603WAF4701T5E"))
    )
    (comp (ref "R16")
      (value "4.7kΩ")
      (footprint "easyedapro:R0603")
      (fields
        (field (name "Manufacturer Part") "0603WAF4701T5E")
        (field (name "Manufacturer") "UNI-ROYAL(厚声)")
      )
      (libsource (lib "easyedapro") (part "0603WAF4701T5E"))
    )
    (comp (ref "R22")
      (value "2.2kΩ")
      (fields
        (field (name "Manufacturer Part") "0603WAF2201T5E")
        (field (name "Manufacturer") "UNI-ROYAL(厚声)")
      )
      (libsource (lib "easyedapro") (part "0805W8J0202T5E"))
    )
    (comp (ref "R23")
      (value "2.2kΩ")
      (fields
        (field (name "Manufacturer Part") "0603WAF2201T5E")
        (field (name "Manufacturer") "UNI-ROYAL(厚声)")
      )
      (libsource (lib "easyedapro") (part "0805W8J0202T5E"))
    )
    (comp (ref "R24")
      (value "2.2kΩ")
      (fields
        (field (name "Manufacturer Part") "0603WAF2201T5E")
        (field (name "Manufacturer") "UNI-ROYAL(厚声)")
      )
      (libsource (lib "easyedapro") (part "0805W8J0202T5E"))
    )
    (comp (ref "R25")
      (value "2.2kΩ")
      (fields
        (field (name "Manufacturer Part") "0603WAF2201T5E")
        (field (name "Manufacturer") "UNI-ROYAL(厚声)")
      )
      (libsource (lib "easyedapro") (part "0805W8J0202T5E"))
    )
    (comp (ref "R26")
      (value "2.2kΩ")
      (fields
        (field (name "Manufacturer Part") "0603WAF2201T5E")
        (field (name "Manufacturer") "UNI-ROYAL(厚声)")
      )
      (libsource (lib "easyedapro") (part "0805W8J0202T5E"))
    )
    (comp (ref "R27")
      (value "2.2kΩ")
      (fields
        (field (name "Manufacturer Part") "0603WAF2201T5E")
        (field (name "Manufacturer") "UNI-ROYAL(厚声)")
      )
      (libsource (lib "easyedapro") (part "0805W8J0202T5E"))
    )
    (comp (ref "R28")
      (value "2.2kΩ")
      (fields
        (field (name "Manufacturer Part") "0603WAF2201T5E")
        (field (name "Manufacturer") "UNI-ROYAL(厚声)")
      )
      (libsource (lib "easyedapro") (part "0805W8J0202T5E"))
    )
    (comp (ref "R29")
      (value "2.2kΩ")
      (fields
        (field (name "Manufacturer Part") "0603WAF2201T5E")
        (field (name "Manufacturer") "UNI-ROYAL(厚声)")
      )
      (libsource (lib "easyedapro") (part "0805W8J0202T5E"))
    )
    (comp (ref "R30")
      (value "2.2kΩ")
      (fields
        (field (name "Manufacturer Part") "0603WAF2201T5E")
        (field (name "Manufacturer") "UNI-ROYAL(厚声)")
      )
      (libsource (lib "easyedapro") (part "0805W8J0202T5E"))
    )
    (comp (ref "R31")
      (value "2.2kΩ")
      (fields
        (field (name "Manufacturer Part") "0603WAF2201T5E")
        (field (name "Manufacturer") "UNI-ROYAL(厚声)")
      )
      (libsource (lib "easyedapro") (part "0805W8J0202T5E"))
    )
    (comp (ref "R32")
      (value "2.2kΩ")
      (fields
        (field (name "Manufacturer Part") "0603WAF2201T5E")
        (field (name "Manufacturer") "UNI-ROYAL(厚声)")
      )
      (libsource (lib "easyedapro") (part "0805W8J0202T5E"))
    )
    (comp (ref "R33")
      (value "2.2kΩ")
      (fields
        (field (name "Manufacturer Part") "0603WAF2201T5E")
        (field (name "Manufacturer") "UNI-ROYAL(厚声)")
      )
      (libsource (lib "easyedapro") (part "0805W8J0202T5E"))
    )
    (comp (ref "R34")
      (value "2.2kΩ")
      (fields
        (field (name "Manufacturer Part") "0603WAF2201T5E")
        (field (name "Manufacturer") "UNI-ROYAL(厚声)")
      )
      (libsource (lib "easyedapro") (part "0805W8J0202T5E"))
    )
    (comp (ref "R35")
      (value "2.2kΩ")
      (fields
        (field (name "Manufacturer Part") "0603WAF2201T5E")
        (field (name "Manufacturer") "UNI-ROYAL(厚声)")
      )
      (libsource (lib "easyedapro") (part "0805W8J0202T5E"))
    )
    (comp (ref "R36")
      (value "2.2kΩ")
      (fields
        (field (name "Manufacturer Part") "0603WAF2201T5E")
        (field (name "Manufacturer") "UNI-ROYAL(厚声)")
      )
      (libsource (lib "easyedapro") (part "0805W8J0202T5E"))
    )
    (comp (ref "R37")
      (value "2.2kΩ")
      (fields
        (field (name "Manufacturer Part") "0603WAF2201T5E")
        (field (name "Manufacturer") "UNI-ROYAL(厚声)")
      )
      (libsource (lib "easyedapro") (part "0805W8J0202T5E"))
    )
    (comp (ref "U1")
      (value "CD4067BMT/TR")
      (footprint "easyedapro:TSSOP-24_L7.8-W4.4-P0.65-LS6.4-BL_1")
      (fields (field (name "Manufacturer") "HGSEMI(华冠)"))
      (libsource (lib "easyedapro") (part "CD4067BMT/TR"))
    )
    (comp (ref "U2")
      (value "KH-2.54FH-1X15P-H8.5")
      (footprint "easyedapro:HDR-TH_15P-P2.54-V-F")
      (fields (field (name "Manufacturer") "kinghelm(金航标)"))
      (libsource (lib "easyedapro") (part "KH-2.54FH-1X15P-H8.5"))
    )
    (comp (ref "U3")
      (value "KH-2.54FH-1X15P-H8.5")
      (footprint "easyedapro:HDR-TH_15P-P2.54-V-F")
      (fields (field (name "Manufacturer") "kinghelm(金航标)"))
      (libsource (lib "easyedapro") (part "KH-2.54FH-1X15P-H8.5"))
    )
  )
  (nets
    (net (code "1") (name "+5V") (class "Default")
      (node (ref "ArduinoNano") (pin "27") (pinfunction "+5V_27") (pintype "unspecified"))
      (node (ref "C1") (pin "2") (pinfunction "2_2") (pintype "unspecified"))
      (node (ref "C10") (pin "2") (pinfunction "2_2") (pintype "unspecified"))
      (node (ref "C11") (pin "2") (pinfunction "2_2") (pintype "unspecified"))
      (node (ref "C12") (pin "2") (pinfunction "2_2") (pintype "unspecified"))
      (node (ref "C13") (pin "2") (pinfunction "2_2") (pintype "unspecified"))
      (node (ref "C14") (pin "2") (pinfunction "2_2") (pintype "unspecified"))
      (node (ref "C15") (pin "2") (pinfunction "2_2") (pintype "unspecified"))
      (node (ref "C16") (pin "2") (pinfunction "2_2") (pintype "unspecified"))
      (node (ref "C17") (pin "2") (pinfunction "2_2") (pintype "unspecified"))
      (node (ref "C18") (pin "2") (pinfunction "2_2") (pintype "unspecified"))
      (node (ref "C19") (pin "2") (pinfunction "2_2") (pintype "unspecified"))
      (node (ref "C2") (pin "2") (pinfunction "2_2") (pintype "unspecified"))
      (node (ref "C20") (pin "2") (pinfunction "2_2") (pintype "unspecified"))
      (node (ref "C21") (pin "2") (pinfunction "2_2") (pintype "unspecified"))
      (node (ref "C22") (pin "2") (pinfunction "2_2") (pintype "unspecified"))
      (node (ref "C23") (pin "2") (pinfunction "2_2") (pintype "unspecified"))
      (node (ref "C24") (pin "2") (pinfunction "2_2") (pintype "unspecified"))
      (node (ref "C25") (pin "2") (pinfunction "2_2") (pintype "unspecified"))
      (node (ref "C26") (pin "2") (pinfunction "2_2") (pintype "unspecified"))
      (node (ref "C27") (pin "2") (pinfunction "2_2") (pintype "unspecified"))
      (node (ref "C28") (pin "2") (pinfunction "2_2") (pintype "unspecified"))
      (node (ref "C29") (pin "2") (pinfunction "2_2") (pintype "unspecified"))
      (node (ref "C3") (pin "2") (pinfunction "2_2") (pintype "unspecified"))
      (node (ref "C30") (pin "2") (pinfunction "2_2") (pintype "unspecified"))
      (node (ref "C31") (pin "2") (pinfunction "2_2") (pintype "unspecified"))
      (node (ref "C32") (pin "2") (pinfunction "2_2") (pintype "unspecified"))
      (node (ref "C33") (pin "2") (pinfunction "2_2") (pintype "unspecified"))
      (node (ref "C34") (pin "2") (pinfunction "2_2") (pintype "unspecified"))
      (node (ref "C35") (pin "2") (pinfunction "2_2") (pintype "unspecified"))
      (node (ref "C36") (pin "2") (pinfunction "2_2") (pintype "unspecified"))
      (node (ref "C37") (pin "2") (pinfunction "2_2") (pintype "unspecified"))
      (node (ref "C38") (pin "2") (pinfunction "2_2") (pintype "unspecified"))
      (node (ref "C39") (pin "2") (pinfunction "2_2") (pintype "unspecified"))
      (node (ref "C4") (pin "2") (pinfunction "2_2") (pintype "unspecified"))
      (node (ref "C40") (pin "2") (pinfunction "2_2") (pintype "unspecified"))
      (node (ref "C41") (pin "2") (pinfunction "2_2") (pintype "unspecified"))
      (node (ref "C42") (pin "2") (pinfunction "2_2") (pintype "unspecified"))
      (node (ref "C43") (pin "2") (pinfunction "2_2") (pintype "unspecified"))
      (node (ref "C44") (pin "2") (pinfunction "2_2") (pintype "unspecified"))
      (node (ref "C45") (pin "2") (pinfunction "2_2") (pintype "unspecified"))
      (node (ref "C46") (pin "2") (pinfunction "2_2") (pintype "unspecified"))
      (node (ref "C47") (pin "2") (pinfunction "2_2") (pintype "unspecified"))
      (node (ref "C48") (pin "2") (pinfunction "2_2") (pintype "unspecified"))
      (node (ref "C5") (pin "2") (pinfunction "2_2") (pintype "unspecified"))
      (node (ref "C6") (pin "2") (pinfunction "2_2") (pintype "unspecified"))
      (node (ref "C7") (pin "2") (pinfunction "2_2") (pintype "unspecified"))
      (node (ref "C8") (pin "2") (pinfunction "2_2") (pintype "unspecified"))
      (node (ref "C9") (pin "2") (pinfunction "2_2") (pintype "unspecified"))
      (node (ref "CMUX") (pin "2") (pinfunction "2_2") (pintype "unspecified"))
      (node (ref "CNANO") (pin "1") (pinfunction "1_1") (pintype "unspecified"))
      (node (ref "CPOWER") (pin "1") (pinfunction "1_1") (pintype "unspecified"))
      (node (ref "LED1") (pin "3") (pinfunction "VDD_3") (pintype "unspecified"))
      (node (ref "LED10") (pin "3") (pinfunction "VDD_3") (pintype "unspecified"))
      (node (ref "LED11") (pin "3") (pinfunction "VDD_3") (pintype "unspecified"))
      (node (ref "LED12") (pin "3") (pinfunction "VDD_3") (pintype "unspecified"))
      (node (ref "LED13") (pin "3") (pinfunction "VDD_3") (pintype "unspecified"))
      (node (ref "LED14") (pin "3") (pinfunction "VDD_3") (pintype "unspecified"))
      (node (ref "LED15") (pin "3") (pinfunction "VDD_3") (pintype "unspecified"))
      (node (ref "LED16") (pin "3") (pinfunction "VDD_3") (pintype "unspecified"))
      (node (ref "LED17") (pin "3") (pinfunction "VDD_3") (pintype "unspecified"))
      (node (ref "LED18") (pin "3") (pinfunction "VDD_3") (pintype "unspecified"))
      (node (ref "LED19") (pin "3") (pinfunction "VDD_3") (pintype "unspecified"))
      (node (ref "LED2") (pin "3") (pinfunction "VDD_3") (pintype "unspecified"))
      (node (ref "LED20") (pin "3") (pinfunction "VDD_3") (pintype "unspecified"))
      (node (ref "LED21") (pin "3") (pinfunction "VDD_3") (pintype "unspecified"))
      (node (ref "LED22") (pin "3") (pinfunction "VDD_3") (pintype "unspecified"))
      (node (ref "LED23") (pin "3") (pinfunction "VDD_3") (pintype "unspecified"))
      (node (ref "LED24") (pin "3") (pinfunction "VDD_3") (pintype "unspecified"))
      (node (ref "LED25") (pin "3") (pinfunction "VDD_3") (pintype "unspecified"))
      (node (ref "LED26") (pin "3") (pinfunction "VDD_3") (pintype "unspecified"))
      (node (ref "LED27") (pin "3") (pinfunction "VDD_3") (pintype "unspecified"))
      (node (ref "LED28") (pin "3") (pinfunction "VDD_3") (pintype "unspecified"))
      (node (ref "LED29") (pin "3") (pinfunction "VDD_3") (pintype "unspecified"))
      (node (ref "LED3") (pin "3") (pinfunction "VDD_3") (pintype "unspecified"))
      (node (ref "LED30") (pin "3") (pinfunction "VDD_3") (pintype "unspecified"))
      (node (ref "LED31") (pin "3") (pinfunction "VDD_3") (pintype "unspecified"))
      (node (ref "LED32") (pin "3") (pinfunction "VDD_3") (pintype "unspecified"))
      (node (ref "LED33") (pin "3") (pinfunction "VDD_3") (pintype "unspecified"))
      (node (ref "LED34") (pin "3") (pinfunction "VDD_3") (pintype "unspecified"))
      (node (ref "LED35") (pin "3") (pinfunction "VDD_3") (pintype "unspecified"))
      (node (ref "LED36") (pin "3") (pinfunction "VDD_3") (pintype "unspecified"))
      (node (ref "LED37") (pin "3") (pinfunction "VDD_3") (pintype "unspecified"))
      (node (ref "LED38") (pin "3") (pinfunction "VDD_3") (pintype "unspecified"))
      (node (ref "LED39") (pin "3") (pinfunction "VDD_3") (pintype "unspecified"))
      (node (ref "LED4") (pin "3") (pinfunction "VDD_3") (pintype "unspecified"))
      (node (ref "LED40") (pin "3") (pinfunction "VDD_3") (pintype "unspecified"))
      (node (ref "LED41") (pin "3") (pinfunction "VDD_3") (pintype "unspecified"))
      (node (ref "LED42") (pin "3") (pinfunction "VDD_3") (pintype "unspecified"))
      (node (ref "LED43") (pin "3") (pinfunction "VDD_3") (pintype "unspecified"))
      (node (ref "LED44") (pin "3") (pinfunction "VDD_3") (pintype "unspecified"))
      (node (ref "LED45") (pin "3") (pinfunction "VDD_3") (pintype "unspecified"))
      (node (ref "LED46") (pin "3") (pinfunction "VDD_3") (pintype "unspecified"))
      (node (ref "LED47") (pin "3") (pinfunction "VDD_3") (pintype "unspecified"))
      (node (ref "LED48") (pin "3") (pinfunction "VDD_3") (pintype "unspecified"))
      (node (ref "LED5") (pin "3") (pinfunction "VDD_3") (pintype "unspecified"))
      (node (ref "LED6") (pin "3") (pinfunction "VDD_3") (pintype "unspecified"))
      (node (ref "LED7") (pin "3") (pinfunction "VDD_3") (pintype "unspecified"))
      (node (ref "LED8") (pin "3") (pinfunction "VDD_3") (pintype "unspecified"))
      (node (ref "LED9") (pin "3") (pinfunction "VDD_3") (pintype "unspecified"))
      (node (ref "Q1") (pin "2") (pinfunction "C_2") (pintype "unspecified"))
      (node (ref "Q10") (pin "2") (pinfunction "C_2") (pintype "unspecified"))
      (node (ref "Q11") (pin "2") (pinfunction "C_2") (pintype "unspecified"))
      (node (ref "Q12") (pin "2") (pinfunction "C_2") (pintype "unspecified"))
      (node (ref "Q13") (pin "2") (pinfunction "C_2") (pintype "unspecified"))
      (node (ref "Q14") (pin "2") (pinfunction "C_2") (pintype "unspecified"))
      (node (ref "Q15") (pin "2") (pinfunction "C_2") (pintype "unspecified"))
      (node (ref "Q16") (pin "2") (pinfunction "C_2") (pintype "unspecified"))
      (node (ref "Q2") (pin "2") (pinfunction "C_2") (pintype "unspecified"))
      (node (ref "Q3") (pin "2") (pinfunction "C_2") (pintype "unspecified"))
      (node (ref "Q4") (pin "2") (pinfunction "C_2") (pintype "unspecified"))
      (node (ref "Q5") (pin "2") (pinfunction "C_2") (pintype "unspecified"))
      (node (ref "Q6") (pin "2") (pinfunction "C_2") (pintype "unspecified"))
      (node (ref "Q7") (pin "2") (pinfunction "C_2") (pintype "unspecified"))
      (node (ref "Q8") (pin "2") (pinfunction "C_2") (pintype "unspecified"))
      (node (ref "Q9") (pin "2") (pinfunction "C_2") (pintype "unspecified"))
      (node (ref "U1") (pin "24") (pinfunction "VCC_24") (pintype "unspecified"))
      (node (ref "U3") (pin "4") (pinfunction "4_4") (pintype "unspecified"))
    )
    (net (code "2") (name "GND") (class "Default")
      (node (ref "ArduinoNano") (pin "29") (pinfunction "GND_29") (pintype "unspecified"))
      (node (ref "ArduinoNano") (pin "4") (pinfunction "GND_4") (pintype "unspecified"))
      (node (ref "C1") (pin "1") (pinfunction "1_1") (pintype "unspecified"))
      (node (ref "C10") (pin "1") (pinfunction "1_1") (pintype "unspecified"))
      (node (ref "C11") (pin "1") (pinfunction "1_1") (pintype "unspecified"))
      (node (ref "C12") (pin "1") (pinfunction "1_1") (pintype "unspecified"))
      (node (ref "C13") (pin "1") (pinfunction "1_1") (pintype "unspecified"))
      (node (ref "C14") (pin "1") (pinfunction "1_1") (pintype "unspecified"))
      (node (ref "C15") (pin "1") (pinfunction "1_1") (pintype "unspecified"))
      (node (ref "C16") (pin "1") (pinfunction "1_1") (pintype "unspecified"))
      (node (ref "C17") (pin "1") (pinfunction "1_1") (pintype "unspecified"))
      (node (ref "C18") (pin "1") (pinfunction "1_1") (pintype "unspecified"))
      (node (ref "C19") (pin "1") (pinfunction "1_1") (pintype "unspecified"))
      (node (ref "C2") (pin "1") (pinfunction "1_1") (pintype "unspecified"))
      (node (ref "C20") (pin "1") (pinfunction "1_1") (pintype "unspecified"))
      (node (ref "C21") (pin "1") (pinfunction "1_1") (pintype "unspecified"))
      (node (ref "C22") (pin "1") (pinfunction "1_1") (pintype "unspecified"))
      (node (ref "C23") (pin "1") (pinfunction "1_1") (pintype "unspecified"))
      (node (ref "C24") (pin "1") (pinfunction "1_1") (pintype "unspecified"))
      (node (ref "C25") (pin "1") (pinfunction "1_1") (pintype "unspecified"))
      (node (ref "C26") (pin "1") (pinfunction "1_1") (pintype "unspecified"))
      (node (ref "C27") (pin "1") (pinfunction "1_1") (pintype "unspecified"))
      (node (ref "C28") (pin "1") (pinfunction "1_1") (pintype "unspecified"))
      (node (ref "C29") (pin "1") (pinfunction "1_1") (pintype "unspecified"))
      (node (ref "C3") (pin "1") (pinfunction "1_1") (pintype "unspecified"))
      (node (ref "C30") (pin "1") (pinfunction "1_1") (pintype "unspecified"))
      (node (ref "C31") (pin "1") (pinfunction "1_1") (pintype "unspecified"))
      (node (ref "C32") (pin "1") (pinfunction "1_1") (pintype "unspecified"))
      (node (ref "C33") (pin "1") (pinfunction "1_1") (pintype "unspecified"))
      (node (ref "C34") (pin "1") (pinfunction "1_1") (pintype "unspecified"))
      (node (ref "C35") (pin "1") (pinfunction "1_1") (pintype "unspecified"))
      (node (ref "C36") (pin "1") (pinfunction "1_1") (pintype "unspecified"))
      (node (ref "C37") (pin "1") (pinfunction "1_1") (pintype "unspecified"))
      (node (ref "C38") (pin "1") (pinfunction "1_1") (pintype "unspecified"))
      (node (ref "C39") (pin "1") (pinfunction "1_1") (pintype "unspecified"))
      (node (ref "C4") (pin "1") (pinfunction "1_1") (pintype "unspecified"))
      (node (ref "C40") (pin "1") (pinfunction "1_1") (pintype "unspecified"))
      (node (ref "C41") (pin "1") (pinfunction "1_1") (pintype "unspecified"))
      (node (ref "C42") (pin "1") (pinfunction "1_1") (pintype "unspecified"))
      (node (ref "C43") (pin "1") (pinfunction "1_1") (pintype "unspecified"))
      (node (ref "C44") (pin "1") (pinfunction "1_1") (pintype "unspecified"))
      (node (ref "C45") (pin "1") (pinfunction "1_1") (pintype "unspecified"))
      (node (ref "C46") (pin "1") (pinfunction "1_1") (pintype "unspecified"))
      (node (ref "C47") (pin "1") (pinfunction "1_1") (pintype "unspecified"))
      (node (ref "C48") (pin "1") (pinfunction "1_1") (pintype "unspecified"))
      (node (ref "C5") (pin "1") (pinfunction "1_1") (pintype "unspecified"))
      (node (ref "C6") (pin "1") (pinfunction "1_1") (pintype "unspecified"))
      (node (ref "C7") (pin "1") (pinfunction "1_1") (pintype "unspecified"))
      (node (ref "C8") (pin "1") (pinfunction "1_1") (pintype "unspecified"))
      (node (ref "C9") (pin "1") (pinfunction "1_1") (pintype "unspecified"))
      (node (ref "CMUX") (pin "1") (pinfunction "1_1") (pintype "unspecified"))
      (node (ref "CNANO") (pin "2") (pinfunction "2_2") (pintype "unspecified"))
      (node (ref "CPOWER") (pin "2") (pinfunction "2_2") (pintype "unspecified"))
      (node (ref "LED1") (pin "1") (pinfunction "GND_1") (pintype "unspecified"))
      (node (ref "LED10") (pin "1") (pinfunction "GND_1") (pintype "unspecified"))
      (node (ref "LED11") (pin "1") (pinfunction "GND_1") (pintype "unspecified"))
      (node (ref "LED12") (pin "1") (pinfunction "GND_1") (pintype "unspecified"))
      (node (ref "LED13") (pin "1") (pinfunction "GND_1") (pintype "unspecified"))
      (node (ref "LED14") (pin "1") (pinfunction "GND_1") (pintype "unspecified"))
      (node (ref "LED15") (pin "1") (pinfunction "GND_1") (pintype "unspecified"))
      (node (ref "LED16") (pin "1") (pinfunction "GND_1") (pintype "unspecified"))
      (node (ref "LED17") (pin "1") (pinfunction "GND_1") (pintype "unspecified"))
      (node (ref "LED18") (pin "1") (pinfunction "GND_1") (pintype "unspecified"))
      (node (ref "LED19") (pin "1") (pinfunction "GND_1") (pintype "unspecified"))
      (node (ref "LED2") (pin "1") (pinfunction "GND_1") (pintype "unspecified"))
      (node (ref "LED20") (pin "1") (pinfunction "GND_1") (pintype "unspecified"))
      (node (ref "LED21") (pin "1") (pinfunction "GND_1") (pintype "unspecified"))
      (node (ref "LED22") (pin "1") (pinfunction "GND_1") (pintype "unspecified"))
      (node (ref "LED23") (pin "1") (pinfunction "GND_1") (pintype "unspecified"))
      (node (ref "LED24") (pin "1") (pinfunction "GND_1") (pintype "unspecified"))
      (node (ref "LED25") (pin "1") (pinfunction "GND_1") (pintype "unspecified"))
      (node (ref "LED26") (pin "1") (pinfunction "GND_1") (pintype "unspecified"))
      (node (ref "LED27") (pin "1") (pinfunction "GND_1") (pintype "unspecified"))
      (node (ref "LED28") (pin "1") (pinfunction "GND_1") (pintype "unspecified"))
      (node (ref "LED29") (pin "1") (pinfunction "GND_1") (pintype "unspecified"))
      (node (ref "LED3") (pin "1") (pinfunction "GND_1") (pintype "unspecified"))
      (node (ref "LED30") (pin "1") (pinfunction "GND_1") (pintype "unspecified"))
      (node (ref "LED31") (pin "1") (pinfunction "GND_1") (pintype "unspecified"))
      (node (ref "LED32") (pin "1") (pinfunction "GND_1") (pintype "unspecified"))
      (node (ref "LED33") (pin "1") (pinfunction "GND_1") (pintype "unspecified"))
      (node (ref "LED34") (pin "1") (pinfunction "GND_1") (pintype "unspecified"))
      (node (ref "LED35") (pin "1") (pinfunction "GND_1") (pintype "unspecified"))
      (node (ref "LED36") (pin "1") (pinfunction "GND_1") (pintype "unspecified"))
      (node (ref "LED37") (pin "1") (pinfunction "GND_1") (pintype "unspecified"))
      (node (ref "LED38") (pin "1") (pinfunction "GND_1") (pintype "unspecified"))
      (node (ref "LED39") (pin "1") (pinfunction "GND_1") (pintype "unspecified"))
      (node (ref "LED4") (pin "1") (pinfunction "GND_1") (pintype "unspecified"))
      (node (ref "LED40") (pin "1") (pinfunction "GND_1") (pintype "unspecified"))
      (node (ref "LED41") (pin "1") (pinfunction "GND_1") (pintype "unspecified"))
      (node (ref "LED42") (pin "1") (pinfunction "GND_1") (pintype "unspecified"))
      (node (ref "LED43") (pin "1") (pinfunction "GND_1") (pintype "unspecified"))
      (node (ref "LED44") (pin "1") (pinfunction "GND_1") (pintype "unspecified"))
      (node (ref "LED45") (pin "1") (pinfunction "GND_1") (pintype "unspecified"))
      (node (ref "LED46") (pin "1") (pinfunction "GND_1") (pintype "unspecified"))
      (node (ref "LED47") (pin "1") (pinfunction "GND_1") (pintype "unspecified"))
      (node (ref "LED48") (pin "1") (pinfunction "GND_1") (pintype "unspecified"))
      (node (ref "LED5") (pin "1") (pinfunction "GND_1") (pintype "unspecified"))
      (node (ref "LED6") (pin "1") (pinfunction "GND_1") (pintype "unspecified"))
      (node (ref "LED7") (pin "1") (pinfunction "GND_1") (pintype "unspecified"))
      (node (ref "LED8") (pin "1") (pinfunction "GND_1") (pintype "unspecified"))
      (node (ref "LED9") (pin "1") (pinfunction "GND_1") (pintype "unspecified"))
      (node (ref "R1") (pin "2") (pinfunction "2_2") (pintype "input"))
      (node (ref "R10") (pin "2") (pinfunction "2_2") (pintype "input"))
      (node (ref "R11") (pin "2") (pinfunction "2_2") (pintype "input"))
      (node (ref "R12") (pin "2") (pinfunction "2_2") (pintype "input"))
      (node (ref "R13") (pin "2") (pinfunction "2_2") (pintype "input"))
      (node (ref "R14") (pin "2") (pinfunction "2_2") (pintype "input"))
      (node (ref "R15") (pin "2") (pinfunction "2_2") (pintype "input"))
      (node (ref "R16") (pin "2") (pinfunction "2_2") (pintype "input"))
      (node (ref "R2") (pin "2") (pinfunction "2_2") (pintype "input"))
      (node (ref "R22") (pin "2") (pinfunction "2_2") (pintype "input"))
      (node (ref "R23") (pin "2") (pinfunction "2_2") (pintype "input"))
      (node (ref "R24") (pin "2") (pinfunction "2_2") (pintype "input"))
      (node (ref "R25") (pin "2") (pinfunction "2_2") (pintype "input"))
      (node (ref "R26") (pin "2") (pinfunction "2_2") (pintype "input"))
      (node (ref "R27") (pin "2") (pinfunction "2_2") (pintype "input"))
      (node (ref "R28") (pin "2") (pinfunction "2_2") (pintype "input"))
      (node (ref "R29") (pin "2") (pinfunction "2_2") (pintype "input"))
      (node (ref "R3") (pin "2") (pinfunction "2_2") (pintype "input"))
      (node (ref "R30") (pin "2") (pinfunction "2_2") (pintype "input"))
      (node (ref "R31") (pin "2") (pinfunction "2_2") (pintype "input"))
      (node (ref "R32") (pin "2") (pinfunction "2_2") (pintype "input"))
      (node (ref "R33") (pin "2") (pinfunction "2_2") (pintype "input"))
      (node (ref "R34") (pin "2") (pinfunction "2_2") (pintype "input"))
      (node (ref "R35") (pin "2") (pinfunction "2_2") (pintype "input"))
      (node (ref "R36") (pin "2") (pinfunction "2_2") (pintype "input"))
      (node (ref "R37") (pin "2") (pinfunction "2_2") (pintype "input"))
      (node (ref "R4") (pin "2") (pinfunction "2_2") (pintype "input"))
      (node (ref "R5") (pin "2") (pinfunction "2_2") (pintype "input"))
      (node (ref "R6") (pin "2") (pinfunction "2_2") (pintype "input"))
      (node (ref "R7") (pin "2") (pinfunction "2_2") (pintype "input"))
      (node (ref "R8") (pin "2") (pinfunction "2_2") (pintype "input"))
      (node (ref "R9") (pin "2") (pinfunction "2_2") (pintype "input"))
      (node (ref "U1") (pin "12") (pinfunction "GND_12") (pintype "unspecified"))
      (node (ref "U1") (pin "15") (pinfunction "E#_15") (pintype "unspecified"))
      (node (ref "U2") (pin "4") (pinfunction "4_4") (pintype "unspecified"))
      (node (ref "U3") (pin "2") (pinfunction "2_2") (pintype "unspecified"))
    )
    (net (code "3") (name "LED") (class "Default")
      (node (ref "ArduinoNano") (pin "6") (pinfunction "D3_6") (pintype "unspecified"))
      (node (ref "LED1") (pin "2") (pinfunction "DI_2") (pintype "unspecified"))
      (node (ref "U2") (pin "6") (pinfunction "6_6") (pintype "unspecified"))
    )
    (net (code "4") (name "Net-(ArduinoNano-3V3)") (class "Default")
      (node (ref "ArduinoNano") (pin "17") (pinfunction "3V3_17") (pintype "unspecified"))
      (node (ref "U3") (pin "14") (pinfunction "14_14") (pintype "unspecified"))
    )
    (net (code "5") (name "Net-(ArduinoNano-A0)") (class "Default")
      (node (ref "ArduinoNano") (pin "19") (pinfunction "A0_19") (pintype "unspecified"))
      (node (ref "U3") (pin "12") (pinfunction "12_12") (pintype "unspecified"))
    )
    (net (code "6") (name "Net-(ArduinoNano-A1)") (class "Default")
      (node (ref "ArduinoNano") (pin "20") (pinfunction "A1_20") (pintype "unspecified"))
      (node (ref "U1") (pin "1") (pinfunction "COMMON_IN/OUT_1") (pintype "unspecified"))
      (node (ref "U3") (pin "11") (pinfunction "11_11") (pintype "unspecified"))
    )
    (net (code "7") (name "Net-(ArduinoNano-A2)") (class "Default")
      (node (ref "ArduinoNano") (pin "21") (pinfunction "A2_21") (pintype "unspecified"))
      (node (ref "U3") (pin "10") (pinfunction "10_10") (pintype "unspecified"))
    )
    (net (code "8") (name "Net-(ArduinoNano-A3)") (class "Default")
      (node (ref "ArduinoNano") (pin "22") (pinfunction "A3_22") (pintype "unspecified"))
      (node (ref "U3") (pin "9") (pinfunction "9_9") (pintype "unspecified"))
    )
    (net (code "9") (name "Net-(ArduinoNano-A4)") (class "Default")
      (node (ref "ArduinoNano") (pin "23") (pinfunction "A4_23") (pintype "unspecified"))
      (node (ref "CI2CIN") (pin "1") (pinfunction "1_1") (pintype "unspecified"))
      (node (ref "CI2COUT") (pin "1") (pinfunction "1_1") (pintype "unspecified"))
      (node (ref "U3") (pin "8") (pinfunction "8_8") (pintype "unspecified"))
    )
    (net (code "10") (name "Net-(ArduinoNano-A5)") (class "Default")
      (node (ref "ArduinoNano") (pin "24") (pinfunction "A5_24") (pintype "unspecified"))
      (node (ref "CI2CIN") (pin "2") (pinfunction "2_2") (pintype "unspecified"))
      (node (ref "CI2COUT") (pin "2") (pinfunction "2_2") (pintype "unspecified"))
      (node (ref "U3") (pin "7") (pinfunction "7_7") (pintype "unspecified"))
    )
    (net (code "11") (name "Net-(ArduinoNano-A6)") (class "Default")
      (node (ref "ArduinoNano") (pin "25") (pinfunction "A6_25") (pintype "unspecified"))
      (node (ref "U3") (pin "6") (pinfunction "6_6") (pintype "unspecified"))
    )
    (net (code "12") (name "Net-(ArduinoNano-A7)") (class "Default")
      (node (ref "ArduinoNano") (pin "26") (pinfunction "A7_26") (pintype "unspecified"))
      (node (ref "U3") (pin "5") (pinfunction "5_5") (pintype "unspecified"))
    )
    (net (code "13") (name "Net-(ArduinoNano-AREF)") (class "Default")
      (node (ref "ArduinoNano") (pin "18") (pinfunction "AREF_18") (pintype "unspecified"))
      (node (ref "U3") (pin "13") (pinfunction "13_13") (pintype "unspecified"))
    )
    (net (code "14") (name "Net-(ArduinoNano-D0{slash}RX)") (class "Default")
      (node (ref "ArduinoNano") (pin "2") (pinfunction "D0/RX_2") (pintype "unspecified"))
      (node (ref "U2") (pin "2") (pinfunction "2_2") (pintype "unspecified"))
    )
    (net (code "15") (name "Net-(ArduinoNano-D1{slash}TX)") (class "Default")
      (node (ref "ArduinoNano") (pin "1") (pinfunction "D1/TX_1") (pintype "unspecified"))
      (node (ref "U2") (pin "1") (pinfunction "1_1") (pintype "unspecified"))
    )
    (net (code "16") (name "Net-(ArduinoNano-D2)") (class "Default")
      (node (ref "ArduinoNano") (pin "5") (pinfunction "D2_5") (pintype "unspecified"))
      (node (ref "U2") (pin "5") (pinfunction "5_5") (pintype "unspecified"))
    )
    (net (code "17") (name "Net-(ArduinoNano-D4)") (class "Default")
      (node (ref "ArduinoNano") (pin "7") (pinfunction "D4_7") (pintype "unspecified"))
      (node (ref "U2") (pin "7") (pinfunction "7_7") (pintype "unspecified"))
    )
    (net (code "18") (name "Net-(ArduinoNano-D5)") (class "Default")
      (node (ref "ArduinoNano") (pin "8") (pinfunction "D5_8") (pintype "unspecified"))
      (node (ref "U2") (pin "8") (pinfunction "8_8") (pintype "unspecified"))
    )
    (net (code "19") (name "Net-(ArduinoNano-D6)") (class "Default")
      (node (ref "ArduinoNano") (pin "9") (pinfunction "D6_9") (pintype "unspecified"))
      (node (ref "U2") (pin "9") (pinfunction "9_9") (pintype "unspecified"))
    )
    (net (code "20") (name "Net-(ArduinoNano-D7)") (class "Default")
      (node (ref "ArduinoNano") (pin "10") (pinfunction "D7_10") (pintype "unspecified"))
      (node (ref "U2") (pin "10") (pinfunction "10_10") (pintype "unspecified"))
    )
    (net (code "21") (name "Net-(ArduinoNano-D12)") (class "Default")
      (node (ref "ArduinoNano") (pin "15") (pinfunction "D12_15") (pintype "unspecified"))
      (node (ref "U2") (pin "15") (pinfunction "15_15") (pintype "unspecified"))
    )
    (net (code "22") (name "Net-(ArduinoNano-D13)") (class "Default")
      (node (ref "ArduinoNano") (pin "16") (pinfunction "D13_16") (pintype "unspecified"))
      (node (ref "U3") (pin "15") (pinfunction "15_15") (pintype "unspecified"))
    )
    (net (code "23") (name "Net-(ArduinoNano-RESET-Pad3)") (class "Default")
      (node (ref "ArduinoNano") (pin "3") (pinfunction "RESET_3") (pintype "unspecified"))
      (node (ref "U2") (pin "3") (pinfunction "3_3") (pintype "unspecified"))
    )
    (net (code "24") (name "Net-(ArduinoNano-RESET-Pad28)") (class "Default")
      (node (ref "ArduinoNano") (pin "28") (pinfunction "RESET_28") (pintype "unspecified"))
      (node (ref "U3") (pin "3") (pinfunction "3_3") (pintype "unspecified"))
    )
    (net (code "25") (name "Net-(ArduinoNano-VIN)") (class "Default")
      (node (ref "ArduinoNano") (pin "30") (pinfunction "VIN_30") (pintype "unspecified"))
      (node (ref "U3") (pin "1") (pinfunction "1_1") (pintype "unspecified"))
    )
    (net (code "26") (name "Net-(LED1-DO)") (class "Default")
      (node (ref "LED1") (pin "4") (pinfunction "DO_4") (pintype "unspecified"))
      (node (ref "LED2") (pin "2") (pinfunction "DI_2") (pintype "unspecified"))
    )
    (net (code "27") (name "Net-(LED2-DO)") (class "Default")
      (node (ref "LED2") (pin "4") (pinfunction "DO_4") (pintype "unspecified"))
      (node (ref "LED3") (pin "2") (pinfunction "DI_2") (pintype "unspecified"))
    )
    (net (code "28") (name "Net-(LED3-DO)") (class "Default")
      (node (ref "LED3") (pin "4") (pinfunction "DO_4") (pintype "unspecified"))
      (node (ref "LED4") (pin "2") (pinfunction "DI_2") (pintype "unspecified"))
    )
    (net (code "29") (name "Net-(LED4-DO)") (class "Default")
      (node (ref "LED4") (pin "4") (pinfunction "DO_4") (pintype "unspecified"))
      (node (ref "LED5") (pin "2") (pinfunction "DI_2") (pintype "unspecified"))
    )
    (net (code "30") (name "Net-(LED5-DO)") (class "Default")
      (node (ref "LED5") (pin "4") (pinfunction "DO_4") (pintype "unspecified"))
      (node (ref "LED6") (pin "2") (pinfunction "DI_2") (pintype "unspecified"))
    )
    (net (code "31") (name "Net-(LED6-DO)") (class "Default")
      (node (ref "LED6") (pin "4") (pinfunction "DO_4") (pintype "unspecified"))
      (node (ref "LED7") (pin "2") (pinfunction "DI_2") (pintype "unspecified"))
    )
    (net (code "32") (name "Net-(LED7-DO)") (class "Default")
      (node (ref "LED7") (pin "4") (pinfunction "DO_4") (pintype "unspecified"))
      (node (ref "LED8") (pin "2") (pinfunction "DI_2") (pintype "unspecified"))
    )
    (net (code "33") (name "Net-(LED8-DO)") (class "Default")
      (node (ref "LED8") (pin "4") (pinfunction "DO_4") (pintype "unspecified"))
      (node (ref "LED9") (pin "2") (pinfunction "DI_2") (pintype "unspecified"))
    )
    (net (code "34") (name "Net-(LED10-DI)") (class "Default")
      (node (ref "LED10") (pin "2") (pinfunction "DI_2") (pintype "unspecified"))
      (node (ref "LED9") (pin "4") (pinfunction "DO_4") (pintype "unspecified"))
    )
    (net (code "35") (name "Net-(LED10-DO)") (class "Default")
      (node (ref "LED10") (pin "4") (pinfunction "DO_4") (pintype "unspecified"))
      (node (ref "LED11") (pin "2") (pinfunction "DI_2") (pintype "unspecified"))
    )
    (net (code "36") (name "Net-(LED11-DO)") (class "Default")
      (node (ref "LED11") (pin "4") (pinfunction "DO_4") (pintype "unspecified"))
      (node (ref "LED12") (pin "2") (pinfunction "DI_2") (pintype "unspecified"))
    )
    (net (code "37") (name "Net-(LED12-DO)") (class "Default")
      (node (ref "LED12") (pin "4") (pinfunction "DO_4") (pintype "unspecified"))
      (node (ref "LED13") (pin "2") (pinfunction "DI_2") (pintype "unspecified"))
    )
    (net (code "38") (name "Net-(LED13-DO)") (class "Default")
      (node (ref "LED13") (pin "4") (pinfunction "DO_4") (pintype "unspecified"))
      (node (ref "LED14") (pin "2") (pinfunction "DI_2") (pintype "unspecified"))
    )
    (net (code "39") (name "Net-(LED14-DO)") (class "Default")
      (node (ref "LED14") (pin "4") (pinfunction "DO_4") (pintype "unspecified"))
      (node (ref "LED15") (pin "2") (pinfunction "DI_2") (pintype "unspecified"))
    )
    (net (code "40") (name "Net-(LED15-DO)") (class "Default")
      (node (ref "LED15") (pin "4") (pinfunction "DO_4") (pintype "unspecified"))
      (node (ref "LED16") (pin "2") (pinfunction "DI_2") (pintype "unspecified"))
    )
    (net (code "41") (name "Net-(LED16-DO)") (class "Default")
      (node (ref "LED16") (pin "4") (pinfunction "DO_4") (pintype "unspecified"))
      (node (ref "LED17") (pin "2") (pinfunction "DI_2") (pintype "unspecified"))
    )
    (net (code "42") (name "Net-(LED17-DO)") (class "Default")
      (node (ref "LED17") (pin "4") (pinfunction "DO_4") (pintype "unspecified"))
      (node (ref "LED18") (pin "2") (pinfunction "DI_2") (pintype "unspecified"))
    )
    (net (code "43") (name "Net-(LED18-DO)") (class "Default")
      (node (ref "LED18") (pin "4") (pinfunction "DO_4") (pintype "unspecified"))
      (node (ref "LED19") (pin "2") (pinfunction "DI_2") (pintype "unspecified"))
    )
    (net (code "44") (name "Net-(LED19-DO)") (class "Default")
      (node (ref "LED19") (pin "4") (pinfunction "DO_4") (pintype "unspecified"))
      (node (ref "LED20") (pin "2") (pinfunction "DI_2") (pintype "unspecified"))
    )
    (net (code "45") (name "Net-(LED20-DO)") (class "Default")
      (node (ref "LED20") (pin "4") (pinfunction "DO_4") (pintype "unspecified"))
      (node (ref "LED21") (pin "2") (pinfunction "DI_2") (pintype "unspecified"))
    )
    (net (code "46") (name "Net-(LED21-DO)") (class "Default")
      (node (ref "LED21") (pin "4") (pinfunction "DO_4") (pintype "unspecified"))
      (node (ref "LED22") (pin "2") (pinfunction "DI_2") (pintype "unspecified"))
    )
    (net (code "47") (name "Net-(LED22-DO)") (class "Default")
      (node (ref "LED22") (pin "4") (pinfunction "DO_4") (pintype "unspecified"))
      (node (ref "LED23") (pin "2") (pinfunction "DI_2") (pintype "unspecified"))
    )
    (net (code "48") (name "Net-(LED23-DO)") (class "Default")
      (node (ref "LED23") (pin "4") (pinfunction "DO_4") (pintype "unspecified"))
      (node (ref "LED24") (pin "2") (pinfunction "DI_2") (pintype "unspecified"))
    )
    (net (code "49") (name "Net-(LED24-DO)") (class "Default")
      (node (ref "LED24") (pin "4") (pinfunction "DO_4") (pintype "unspecified"))
      (node (ref "LED25") (pin "2") (pinfunction "DI_2") (pintype "unspecified"))
    )
    (net (code "50") (name "Net-(LED25-DO)") (class "Default")
      (node (ref "LED25") (pin "4") (pinfunction "DO_4") (pintype "unspecified"))
      (node (ref "LED26") (pin "2") (pinfunction "DI_2") (pintype "unspecified"))
    )
    (net (code "51") (name "Net-(LED26-DO)") (class "Default")
      (node (ref "LED26") (pin "4") (pinfunction "DO_4") (pintype "unspecified"))
      (node (ref "LED27") (pin "2") (pinfunction "DI_2") (pintype "unspecified"))
    )
    (net (code "52") (name "Net-(LED27-DO)") (class "Default")
      (node (ref "LED27") (pin "4") (pinfunction "DO_4") (pintype "unspecified"))
      (node (ref "LED28") (pin "2") (pinfunction "DI_2") (pintype "unspecified"))
    )
    (net (code "53") (name "Net-(LED28-DO)") (class "Default")
      (node (ref "LED28") (pin "4") (pinfunction "DO_4") (pintype "unspecified"))
      (node (ref "LED29") (pin "2") (pinfunction "DI_2") (pintype "unspecified"))
    )
    (net (code "54") (name "Net-(LED29-DO)") (class "Default")
      (node (ref "LED29") (pin "4") (pinfunction "DO_4") (pintype "unspecified"))
      (node (ref "LED30") (pin "2") (pinfunction "DI_2") (pintype "unspecified"))
    )
    (net (code "55") (name "Net-(LED30-DO)") (class "Default")
      (node (ref "LED30") (pin "4") (pinfunction "DO_4") (pintype "unspecified"))
      (node (ref "LED31") (pin "2") (pinfunction "DI_2") (pintype "unspecified"))
    )
    (net (code "56") (name "Net-(LED31-DO)") (class "Default")
      (node (ref "LED31") (pin "4") (pinfunction "DO_4") (pintype "unspecified"))
      (node (ref "LED32") (pin "2") (pinfunction "DI_2") (pintype "unspecified"))
    )
    (net (code "57") (name "Net-(LED32-DO)") (class "Default")
      (node (ref "LED32") (pin "4") (pinfunction "DO_4") (pintype "unspecified"))
      (node (ref "LED33") (pin "2") (pinfunction "DI_2") (pintype "unspecified"))
    )
    (net (code "58") (name "Net-(LED33-DO)") (class "Default")
      (node (ref "LED33") (pin "4") (pinfunction "DO_4") (pintype "unspecified"))
      (node (ref "LED34") (pin "2") (pinfunction "DI_2") (pintype "unspecified"))
    )
    (net (code "59") (name "Net-(LED34-DO)") (class "Default")
      (node (ref "LED34") (pin "4") (pinfunction "DO_4") (pintype "unspecified"))
      (node (ref "LED35") (pin "2") (pinfunction "DI_2") (pintype "unspecified"))
    )
    (net (code "60") (name "Net-(LED35-DO)") (class "Default")
      (node (ref "LED35") (pin "4") (pinfunction "DO_4") (pintype "unspecified"))
      (node (ref "LED36") (pin "2") (pinfunction "DI_2") (pintype "unspecified"))
    )
    (net (code "61") (name "Net-(LED36-DO)") (class "Default")
      (node (ref "LED36") (pin "4") (pinfunction "DO_4") (pintype "unspecified"))
      (node (ref "LED37") (pin "2") (pinfunction "DI_2") (pintype "unspecified"))
    )
    (net (code "62") (name "Net-(LED37-DO)") (class "Default")
      (node (ref "LED37") (pin "4") (pinfunction "DO_4") (pintype "unspecified"))
      (node (ref "LED38") (pin "2") (pinfunction "DI_2") (pintype "unspecified"))
    )
    (net (code "63") (name "Net-(LED38-DO)") (class "Default")
      (node (ref "LED38") (pin "4") (pinfunction "DO_4") (pintype "unspecified"))
      (node (ref "LED39") (pin "2") (pinfunction "DI_2") (pintype "unspecified"))
    )
    (net (code "64") (name "Net-(LED39-DO)") (class "Default")
      (node (ref "LED39") (pin "4") (pinfunction "DO_4") (pintype "unspecified"))
      (node (ref "LED40") (pin "2") (pinfunction "DI_2") (pintype "unspecified"))
    )
    (net (code "65") (name "Net-(LED40-DO)") (class "Default")
      (node (ref "LED40") (pin "4") (pinfunction "DO_4") (pintype "unspecified"))
      (node (ref "LED41") (pin "2") (pinfunction "DI_2") (pintype "unspecified"))
    )
    (net (code "66") (name "Net-(LED41-DO)") (class "Default")
      (node (ref "LED41") (pin "4") (pinfunction "DO_4") (pintype "unspecified"))
      (node (ref "LED42") (pin "2") (pinfunction "DI_2") (pintype "unspecified"))
    )
    (net (code "67") (name "Net-(LED42-DO)") (class "Default")
      (node (ref "LED42") (pin "4") (pinfunction "DO_4") (pintype "unspecified"))
      (node (ref "LED43") (pin "2") (pinfunction "DI_2") (pintype "unspecified"))
    )
    (net (code "68") (name "Net-(LED43-DO)") (class "Default")
      (node (ref "LED43") (pin "4") (pinfunction "DO_4") (pintype "unspecified"))
      (node (ref "LED44") (pin "2") (pinfunction "DI_2") (pintype "unspecified"))
    )
    (net (code "69") (name "Net-(LED44-DO)") (class "Default")
      (node (ref "LED44") (pin "4") (pinfunction "DO_4") (pintype "unspecified"))
      (node (ref "LED45") (pin "2") (pinfunction "DI_2") (pintype "unspecified"))
    )
    (net (code "70") (name "Net-(LED45-DO)") (class "Default")
      (node (ref "LED45") (pin "4") (pinfunction "DO_4") (pintype "unspecified"))
      (node (ref "LED46") (pin "2") (pinfunction "DI_2") (pintype "unspecified"))
    )
    (net (code "71") (name "Net-(LED46-DO)") (class "Default")
      (node (ref "LED46") (pin "4") (pinfunction "DO_4") (pintype "unspecified"))
      (node (ref "LED47") (pin "2") (pinfunction "DI_2") (pintype "unspecified"))
    )
    (net (code "72") (name "Net-(LED47-DO)") (class "Default")
      (node (ref "LED47") (pin "4") (pinfunction "DO_4") (pintype "unspecified"))
      (node (ref "LED48") (pin "2") (pinfunction "DI_2") (pintype "unspecified"))
    )
    (net (code "73") (name "PHOTO_1.1") (class "Default")
      (node (ref "Q1") (pin "1") (pinfunction "E_1") (pintype "unspecified"))
      (node (ref "R1") (pin "1") (pinfunction "1_1") (pintype "input"))
      (node (ref "R22") (pin "1") (pinfunction "1_1") (pintype "input"))
      (node (ref "U1") (pin "2") (pinfunction "I7_2") (pintype "unspecified"))
    )
    (net (code "74") (name "PHOTO_1.2") (class "Default")
      (node (ref "Q2") (pin "1") (pinfunction "E_1") (pintype "unspecified"))
      (node (ref "R2") (pin "1") (pinfunction "1_1") (pintype "input"))
      (node (ref "R23") (pin "1") (pinfunction "1_1") (pintype "input"))
      (node (ref "U1") (pin "3") (pinfunction "I6_3") (pintype "unspecified"))
    )
    (net (code "75") (name "PHOTO_1.3") (class "Default")
      (node (ref "Q3") (pin "1") (pinfunction "E_1") (pintype "unspecified"))
      (node (ref "R24") (pin "1") (pinfunction "1_1") (pintype "input"))
      (node (ref "R3") (pin "1") (pinfunction "1_1") (pintype "input"))
      (node (ref "U1") (pin "4") (pinfunction "I5_4") (pintype "unspecified"))
    )
    (net (code "76") (name "PHOTO_1.4") (class "Default")
      (node (ref "Q4") (pin "1") (pinfunction "E_1") (pintype "unspecified"))
      (node (ref "R25") (pin "1") (pinfunction "1_1") (pintype "input"))
      (node (ref "R4") (pin "1") (pinfunction "1_1") (pintype "input"))
      (node (ref "U1") (pin "5") (pinfunction "I4_5") (pintype "unspecified"))
    )
    (net (code "77") (name "PHOTO_2.1") (class "Default")
      (node (ref "Q5") (pin "1") (pinfunction "E_1") (pintype "unspecified"))
      (node (ref "R26") (pin "1") (pinfunction "1_1") (pintype "input"))
      (node (ref "R5") (pin "1") (pinfunction "1_1") (pintype "input"))
      (node (ref "U1") (pin "6") (pinfunction "I3_6") (pintype "unspecified"))
    )
    (net (code "78") (name "PHOTO_2.2") (class "Default")
      (node (ref "Q6") (pin "1") (pinfunction "E_1") (pintype "unspecified"))
      (node (ref "R27") (pin "1") (pinfunction "1_1") (pintype "input"))
      (node (ref "R6") (pin "1") (pinfunction "1_1") (pintype "input"))
      (node (ref "U1") (pin "7") (pinfunction "I2_7") (pintype "unspecified"))
    )
    (net (code "79") (name "PHOTO_2.3") (class "Default")
      (node (ref "Q7") (pin "1") (pinfunction "E_1") (pintype "unspecified"))
      (node (ref "R28") (pin "1") (pinfunction "1_1") (pintype "input"))
      (node (ref "R7") (pin "1") (pinfunction "1_1") (pintype "input"))
      (node (ref "U1") (pin "8") (pinfunction "I1_8") (pintype "unspecified"))
    )
    (net (code "80") (name "PHOTO_2.4") (class "Default")
      (node (ref "Q8") (pin "1") (pinfunction "E_1") (pintype "unspecified"))
      (node (ref "R29") (pin "1") (pinfunction "1_1") (pintype "input"))
      (node (ref "R8") (pin "1") (pinfunction "1_1") (pintype "input"))
      (node (ref "U1") (pin "9") (pinfunction "I0_9") (pintype "unspecified"))
    )
    (net (code "81") (name "PHOTO_3.1") (class "Default")
      (node (ref "Q9") (pin "1") (pinfunction "E_1") (pintype "unspecified"))
      (node (ref "R30") (pin "1") (pinfunction "1_1") (pintype "input"))
      (node (ref "R9") (pin "1") (pinfunction "1_1") (pintype "input"))
      (node (ref "U1") (pin "23") (pinfunction "I8_23") (pintype "unspecified"))
    )
    (net (code "82") (name "PHOTO_3.2") (class "Default")
      (node (ref "Q10") (pin "1") (pinfunction "E_1") (pintype "unspecified"))
      (node (ref "R10") (pin "1") (pinfunction "1_1") (pintype "input"))
      (node (ref "R31") (pin "1") (pinfunction "1_1") (pintype "input"))
      (node (ref "U1") (pin "22") (pinfunction "I9_22") (pintype "unspecified"))
    )
    (net (code "83") (name "PHOTO_3.3") (class "Default")
      (node (ref "Q11") (pin "1") (pinfunction "E_1") (pintype "unspecified"))
      (node (ref "R11") (pin "1") (pinfunction "1_1") (pintype "input"))
      (node (ref "R32") (pin "1") (pinfunction "1_1") (pintype "input"))
      (node (ref "U1") (pin "21") (pinfunction "I10_21") (pintype "unspecified"))
    )
    (net (code "84") (name "PHOTO_3.4") (class "Default")
      (node (ref "Q12") (pin "1") (pinfunction "E_1") (pintype "unspecified"))
      (node (ref "R12") (pin "1") (pinfunction "1_1") (pintype "input"))
      (node (ref "R33") (pin "1") (pinfunction "1_1") (pintype "input"))
      (node (ref "U1") (pin "20") (pinfunction "I11_20") (pintype "unspecified"))
    )
    (net (code "85") (name "PHOTO_4.1") (class "Default")
      (node (ref "Q13") (pin "1") (pinfunction "E_1") (pintype "unspecified"))
      (node (ref "R13") (pin "1") (pinfunction "1_1") (pintype "input"))
      (node (ref "R34") (pin "1") (pinfunction "1_1") (pintype "input"))
      (node (ref "U1") (pin "19") (pinfunction "I12_19") (pintype "unspecified"))
    )
    (net (code "86") (name "PHOTO_4.2") (class "Default")
      (node (ref "Q14") (pin "1") (pinfunction "E_1") (pintype "unspecified"))
      (node (ref "R14") (pin "1") (pinfunction "1_1") (pintype "input"))
      (node (ref "R35") (pin "1") (pinfunction "1_1") (pintype "input"))
      (node (ref "U1") (pin "18") (pinfunction "I13_18") (pintype "unspecified"))
    )
    (net (code "87") (name "PHOTO_4.3") (class "Default")
      (node (ref "Q15") (pin "1") (pinfunction "E_1") (pintype "unspecified"))
      (node (ref "R15") (pin "1") (pinfunction "1_1") (pintype "input"))
      (node (ref "R36") (pin "1") (pinfunction "1_1") (pintype "input"))
      (node (ref "U1") (pin "17") (pinfunction "I14_17") (pintype "unspecified"))
    )
    (net (code "88") (name "PHOTO_4.4") (class "Default")
      (node (ref "Q16") (pin "1") (pinfunction "E_1") (pintype "unspecified"))
      (node (ref "R16") (pin "1") (pinfunction "1_1") (pintype "input"))
      (node (ref "R37") (pin "1") (pinfunction "1_1") (pintype "input"))
      (node (ref "U1") (pin "16") (pinfunction "I15_16") (pintype "unspecified"))
    )
    (net (code "89") (name "PHOTO_IN_1") (class "Default")
      (node (ref "ArduinoNano") (pin "11") (pinfunction "D8_11") (pintype "unspecified"))
      (node (ref "U1") (pin "10") (pinfunction "S0_10") (pintype "unspecified"))
      (node (ref "U2") (pin "11") (pinfunction "11_11") (pintype "unspecified"))
    )
    (net (code "90") (name "PHOTO_IN_2") (class "Default")
      (node (ref "ArduinoNano") (pin "12") (pinfunction "D9_12") (pintype "unspecified"))
      (node (ref "U1") (pin "11") (pinfunction "S1_11") (pintype "unspecified"))
      (node (ref "U2") (pin "12") (pinfunction "12_12") (pintype "unspecified"))
    )
    (net (code "91") (name "PHOTO_IN_3") (class "Default")
      (node (ref "ArduinoNano") (pin "13") (pinfunction "D10_13") (pintype "unspecified"))
      (node (ref "U1") (pin "14") (pinfunction "S2_14") (pintype "unspecified"))
      (node (ref "U2") (pin "13") (pinfunction "13_13") (pintype "unspecified"))
    )
    (net (code "92") (name "PHOTO_IN_4") (class "Default")
      (node (ref "ArduinoNano") (pin "14") (pinfunction "D11_14") (pintype "unspecified"))
      (node (ref "U1") (pin "13") (pinfunction "S3_13") (pintype "unspecified"))
      (node (ref "U2") (pin "14") (pinfunction "14_14") (pintype "unspecified"))
    )
    (net (code "93") (name "unconnected-(LED48-DO-Pad4)") (class "Default")
      (node (ref "LED48") (pin "4") (pinfunction "DO_4") (pintype "unspecified"))
    )
  )
)
